# MTX_Tap_an_er_V11.net
KiCad netlist of a schematic drawn in EAGLE
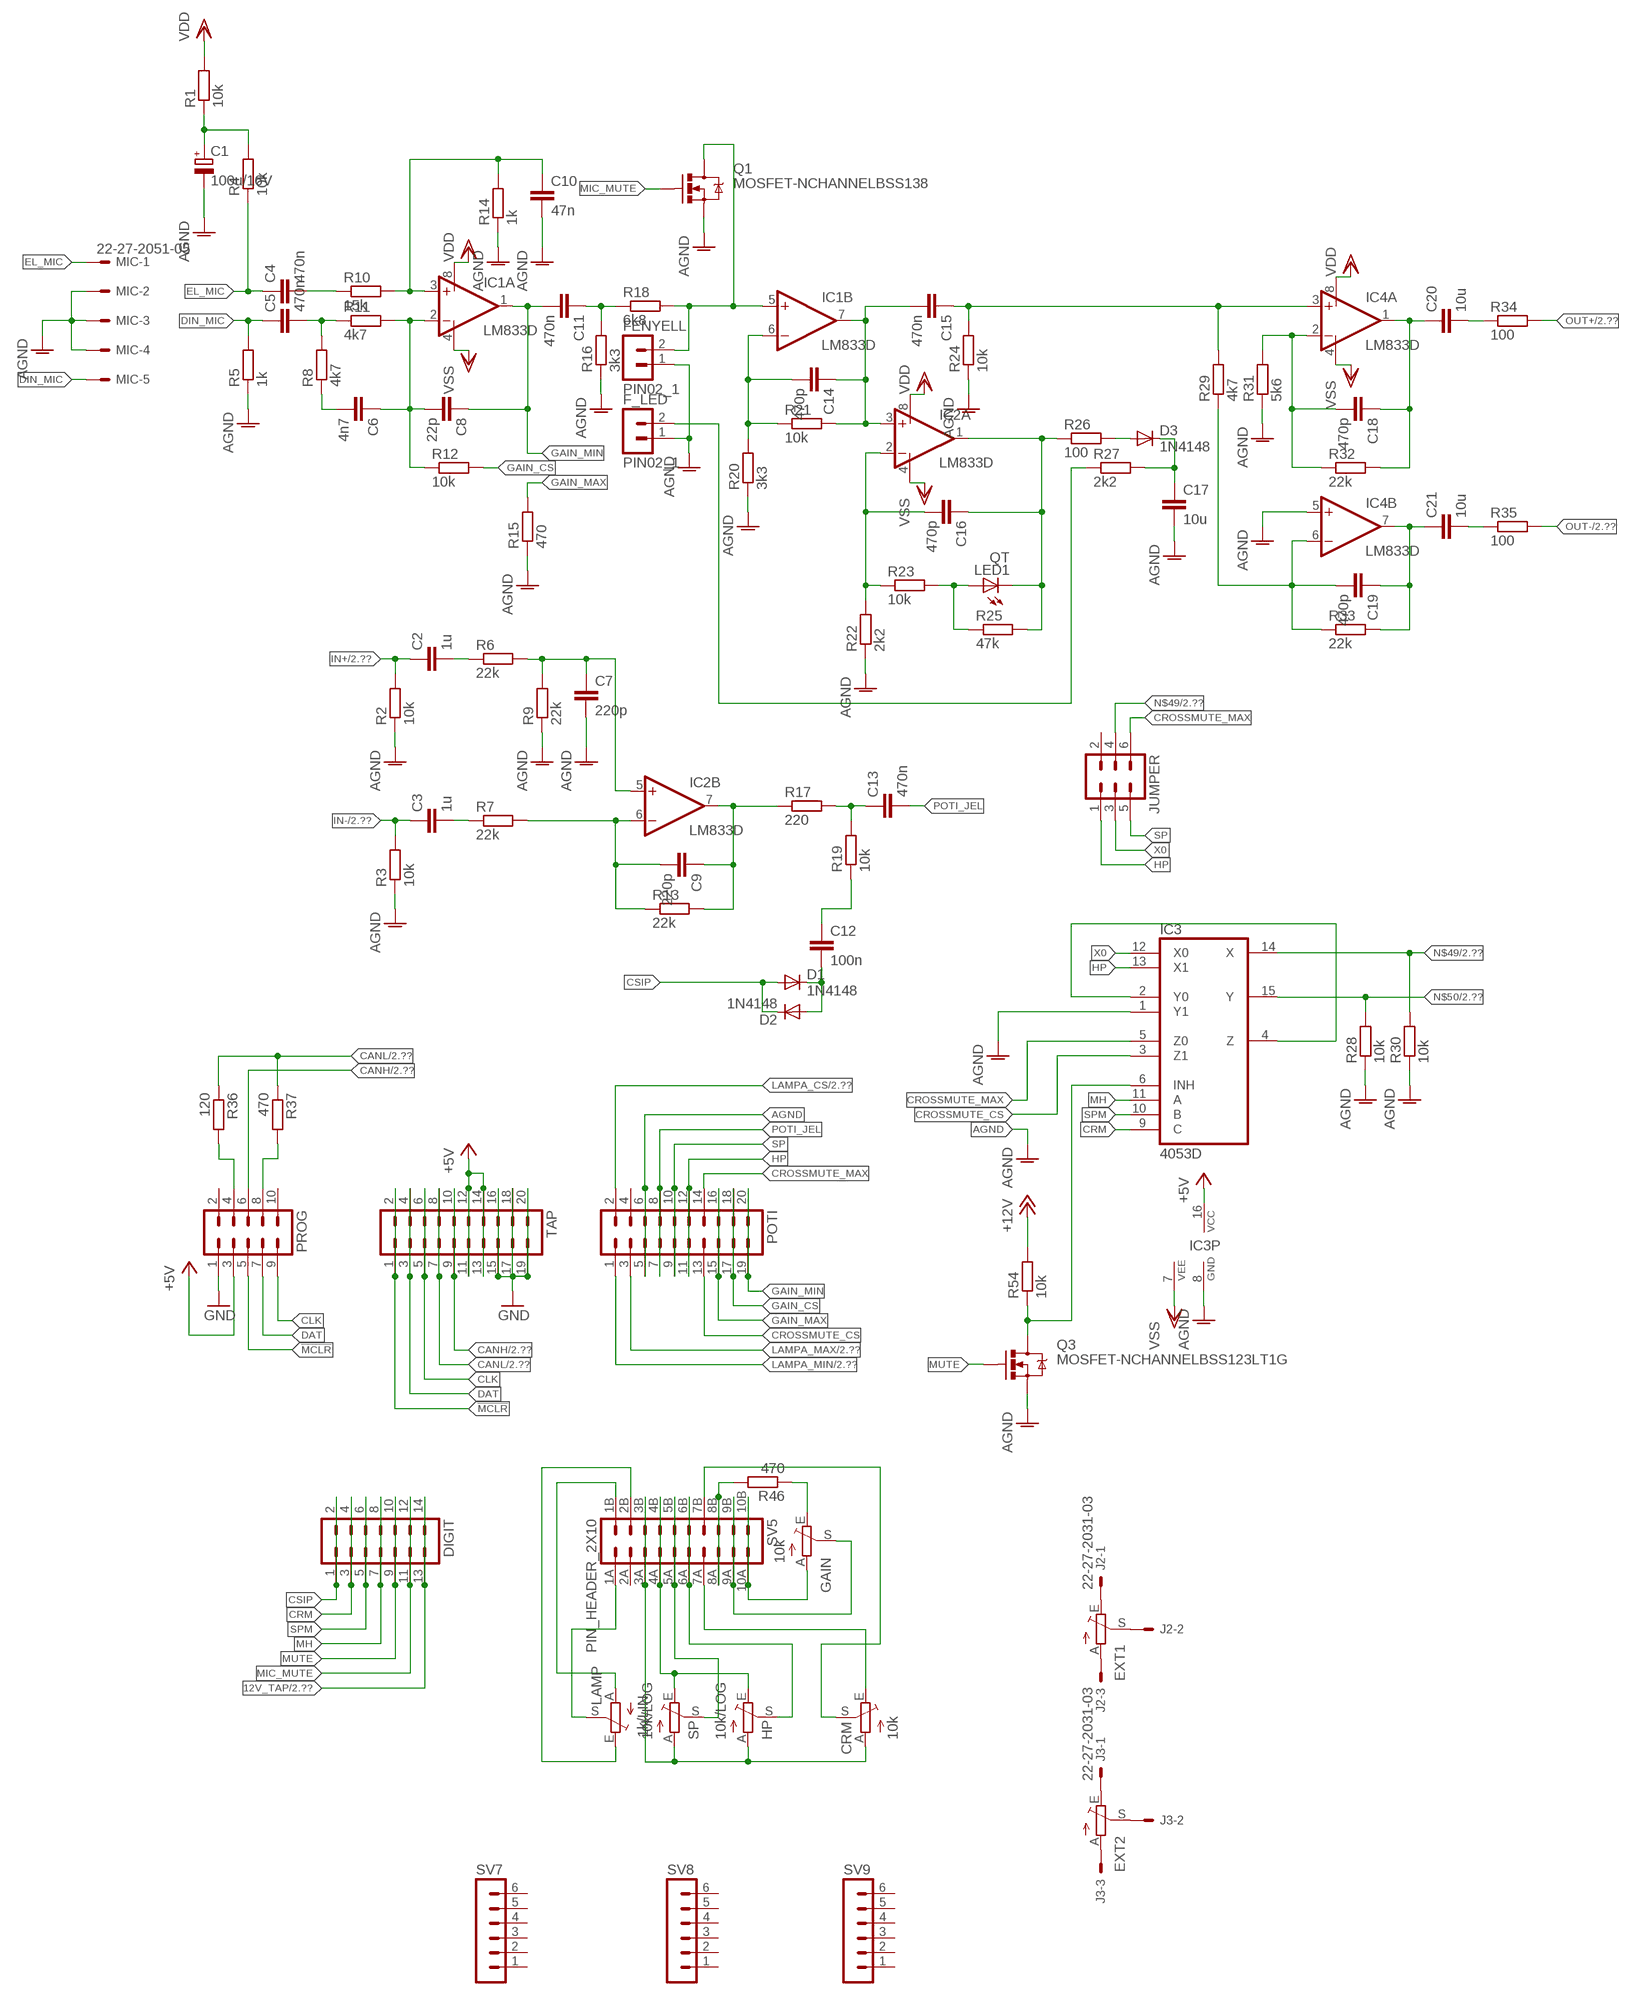
[diagram p0: schematic, sheet 1]
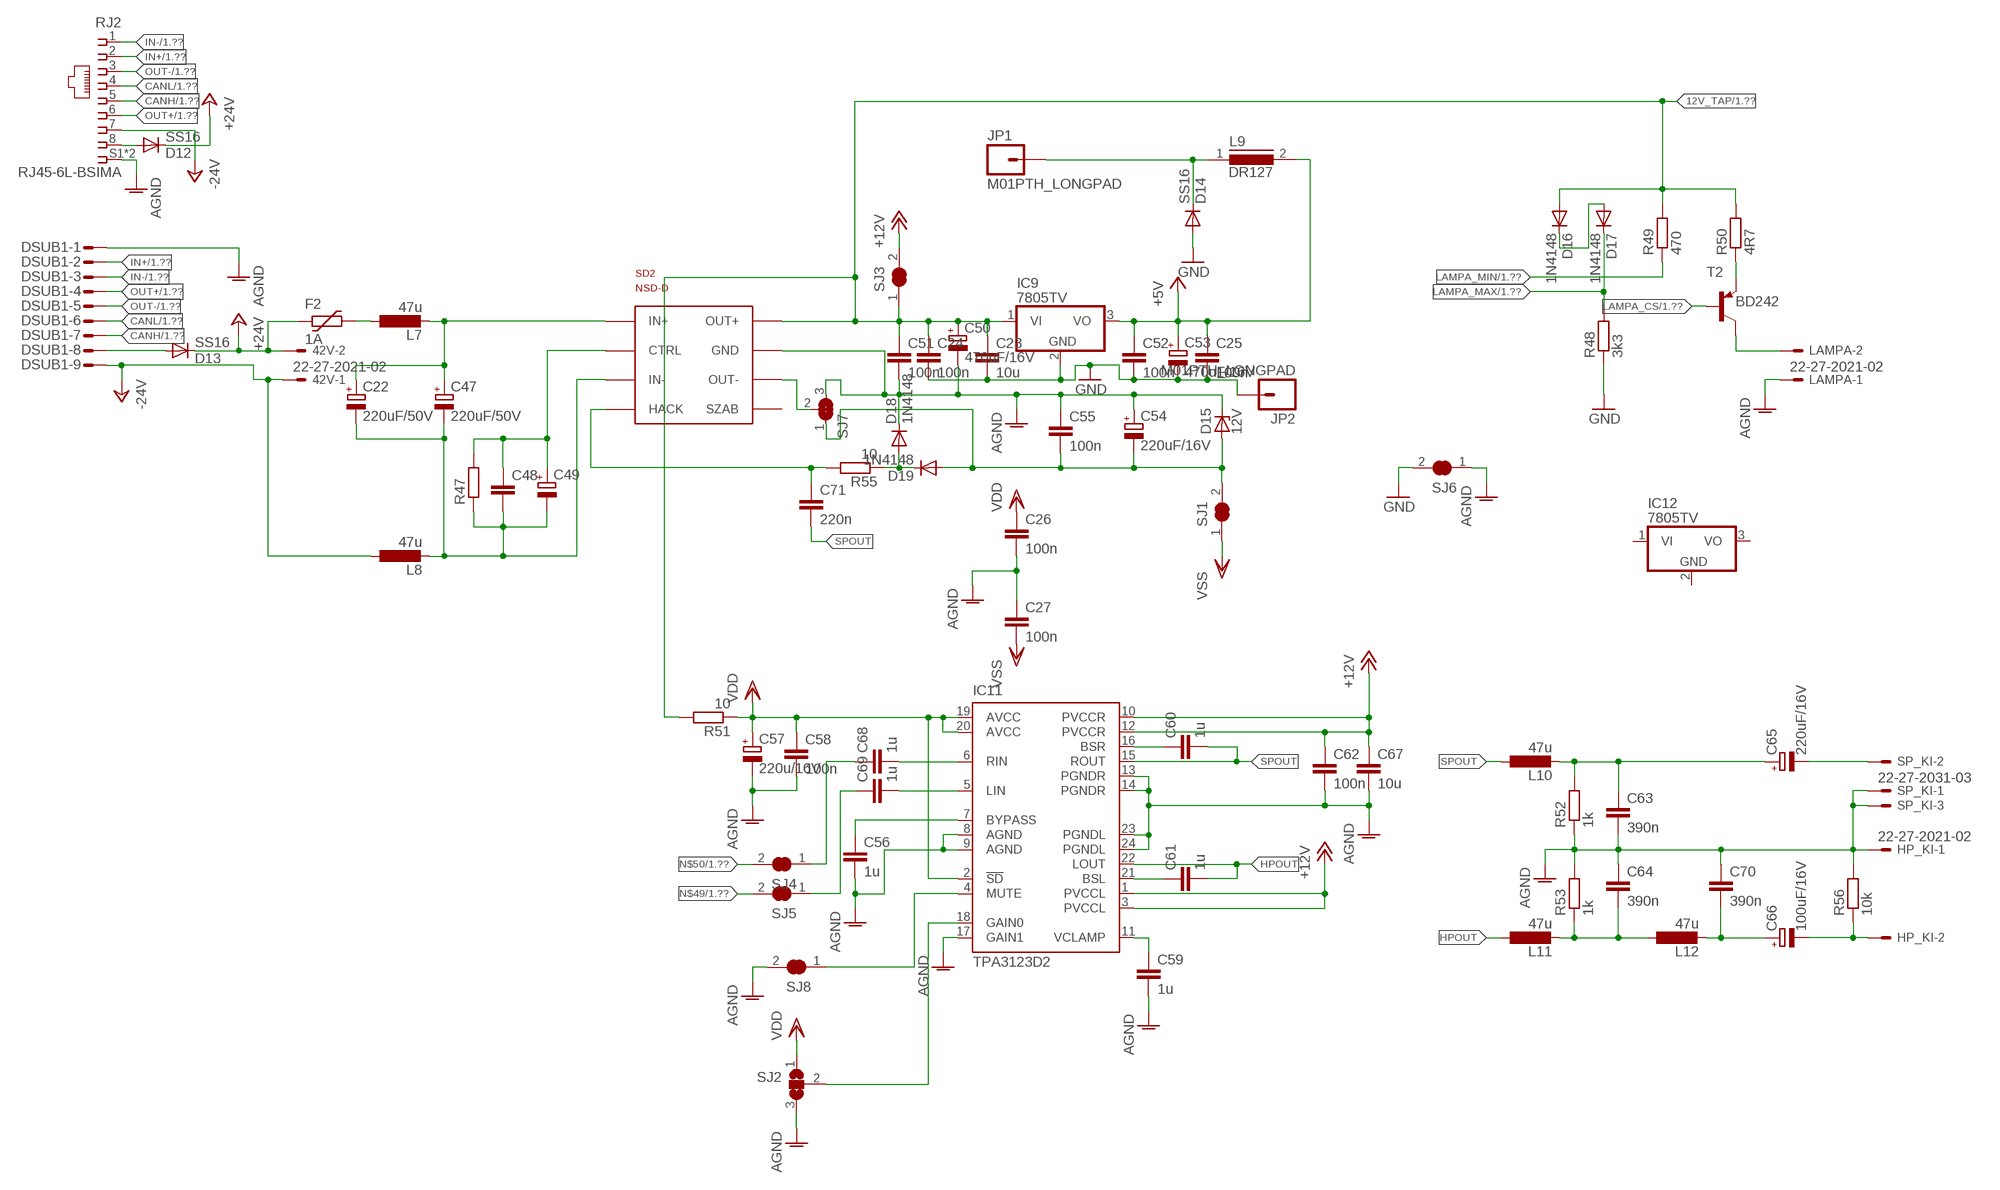
[diagram p1: schematic, sheet 2]

(export (version "E")
  (design (tool "Eeschema 10.0.6"))
  (components
    (comp (ref "42V")
      (value "22-27-2021-02")
      (footprint "eagle-import:6410-02")
      (libsource (lib "eagle-import") (part "22-?-0227-2021"))
    )
    (comp (ref "C22")
      (value "220uF/50V")
      (footprint "eagle-import:E3,5-8")
      (libsource (lib "eagle-import") (part "CPOL-EUE3.5-8"))
    )
    (comp (ref "C23")
      (value "10u")
      (footprint "eagle-import:C0805")
      (libsource (lib "eagle-import") (part "C-EUC0805"))
    )
    (comp (ref "C24")
      (value "100n")
      (footprint "eagle-import:C0805")
      (libsource (lib "eagle-import") (part "C-EUC0805"))
    )
    (comp (ref "C25")
      (value "100n")
      (footprint "eagle-import:C0805")
      (libsource (lib "eagle-import") (part "C-EUC0805"))
    )
    (comp (ref "C26")
      (value "100n")
      (footprint "eagle-import:C0805")
      (libsource (lib "eagle-import") (part "C-EUC0805"))
    )
    (comp (ref "C27")
      (value "100n")
      (footprint "eagle-import:C0805")
      (libsource (lib "eagle-import") (part "C-EUC0805"))
    )
    (comp (ref "C47")
      (value "220uF/50V")
      (footprint "eagle-import:E3,5-8")
      (libsource (lib "eagle-import") (part "CPOL-EUE3.5-8"))
    )
    (comp (ref "C48")
      (value "C-EUC0805")
      (footprint "eagle-import:C0805")
      (libsource (lib "eagle-import") (part "C-EUC0805"))
    )
    (comp (ref "C49")
      (value "CPOL-EUE2.5-5")
      (footprint "eagle-import:E2,5-5")
      (libsource (lib "eagle-import") (part "CPOL-EUE2.5-5"))
    )
    (comp (ref "C50")
      (value "470uF/16V")
      (footprint "eagle-import:E3,5-8")
      (libsource (lib "eagle-import") (part "CPOL-EUE3.5-8"))
    )
    (comp (ref "C51")
      (value "100n")
      (footprint "eagle-import:C0805")
      (libsource (lib "eagle-import") (part "C-EUC0805"))
    )
    (comp (ref "C52")
      (value "100n")
      (footprint "eagle-import:C0805")
      (libsource (lib "eagle-import") (part "C-EUC0805"))
    )
    (comp (ref "C53")
      (value "470uF/16V")
      (footprint "eagle-import:E3,5-8")
      (libsource (lib "eagle-import") (part "CPOL-EUE3.5-8"))
    )
    (comp (ref "C54")
      (value "220uF/16V")
      (footprint "eagle-import:E2,5-7")
      (libsource (lib "eagle-import") (part "CPOL-EUE2.5-7"))
    )
    (comp (ref "C55")
      (value "100n")
      (footprint "eagle-import:C0805")
      (libsource (lib "eagle-import") (part "C-EUC0805"))
    )
    (comp (ref "C56")
      (value "1u")
      (footprint "eagle-import:C0805")
      (libsource (lib "eagle-import") (part "C-EUC0805"))
    )
    (comp (ref "C57")
      (value "220u/16V")
      (footprint "eagle-import:E2,5-7")
      (libsource (lib "eagle-import") (part "CPOL-EUE2.5-7"))
    )
    (comp (ref "C58")
      (value "100n")
      (footprint "eagle-import:C0805")
      (libsource (lib "eagle-import") (part "C-EUC0805"))
    )
    (comp (ref "C59")
      (value "1u")
      (footprint "eagle-import:C0805")
      (libsource (lib "eagle-import") (part "C-EUC0805"))
    )
    (comp (ref "C60")
      (value "1u")
      (footprint "eagle-import:C0805")
      (libsource (lib "eagle-import") (part "C-EUC0805"))
    )
    (comp (ref "C61")
      (value "1u")
      (footprint "eagle-import:C0805")
      (libsource (lib "eagle-import") (part "C-EUC0805"))
    )
    (comp (ref "C62")
      (value "100n")
      (footprint "eagle-import:C0805")
      (libsource (lib "eagle-import") (part "C-EUC0805"))
    )
    (comp (ref "C63")
      (value "390n")
      (footprint "eagle-import:C0805")
      (libsource (lib "eagle-import") (part "C-EUC0805"))
    )
    (comp (ref "C64")
      (value "390n")
      (footprint "eagle-import:C0805")
      (libsource (lib "eagle-import") (part "C-EUC0805"))
    )
    (comp (ref "C65")
      (value "220uF/16V")
      (footprint "eagle-import:E2,5-7")
      (libsource (lib "eagle-import") (part "CPOL-EUE2.5-7"))
    )
    (comp (ref "C66")
      (value "100uF/16V")
      (footprint "eagle-import:E2,5-6")
      (libsource (lib "eagle-import") (part "CPOL-EUE2.5-6"))
    )
    (comp (ref "C67")
      (value "10u")
      (footprint "eagle-import:C0805")
      (libsource (lib "eagle-import") (part "C-EUC0805"))
    )
    (comp (ref "C68")
      (value "1u")
      (footprint "eagle-import:C0805")
      (libsource (lib "eagle-import") (part "C-EUC0805"))
    )
    (comp (ref "C69")
      (value "1u")
      (footprint "eagle-import:C0805")
      (libsource (lib "eagle-import") (part "C-EUC0805"))
    )
    (comp (ref "C70")
      (value "390n")
      (footprint "eagle-import:C0805")
      (libsource (lib "eagle-import") (part "C-EUC0805"))
    )
    (comp (ref "C71")
      (value "220n")
      (footprint "eagle-import:C0805")
      (libsource (lib "eagle-import") (part "C-EUC0805"))
    )
    (comp (ref "D12")
      (value "SS16")
      (footprint "eagle-import:DO-214AC")
      (libsource (lib "eagle-import") (part "dp_devices_DIODE-DO-214AC"))
    )
    (comp (ref "D13")
      (value "SS16")
      (footprint "eagle-import:DO-214AC")
      (libsource (lib "eagle-import") (part "dp_devices_DIODE-DO-214AC"))
    )
    (comp (ref "D14")
      (value "SS16")
      (footprint "eagle-import:DO-214AC")
      (libsource (lib "eagle-import") (part "dp_devices_DIODE-DO-214AC"))
    )
    (comp (ref "D15")
      (value "12V")
      (footprint "eagle-import:SOD80C")
      (libsource (lib "eagle-import") (part "ZENER-DIODESOD80C"))
    )
    (comp (ref "D16")
      (value "1N4148")
      (footprint "eagle-import:SOD80C")
      (libsource (lib "eagle-import") (part "DIODE-SOD80C"))
    )
    (comp (ref "D17")
      (value "1N4148")
      (footprint "eagle-import:SOD80C")
      (libsource (lib "eagle-import") (part "DIODE-SOD80C"))
    )
    (comp (ref "D18")
      (value "1N4148")
      (footprint "eagle-import:SOD80C")
      (libsource (lib "eagle-import") (part "DIODE-SOD80C"))
    )
    (comp (ref "D19")
      (value "1N4148")
      (footprint "eagle-import:SOD80C")
      (libsource (lib "eagle-import") (part "DIODE-SOD80C"))
    )
    (comp (ref "DSUB1")
      (value "M09-182S")
      (footprint "eagle-import:182-009-MALE")
      (libsource (lib "eagle-import") (part "M09?S-182"))
    )
    (comp (ref "F2")
      (value "1A")
      (footprint "eagle-import:PTC1812L")
      (libsource (lib "eagle-import") (part "FUSE_PTC-1812"))
    )
    (comp (ref "HP_KI")
      (value "22-27-2021-02")
      (footprint "eagle-import:6410-02")
      (libsource (lib "eagle-import") (part "22-?-0227-2021"))
    )
    (comp (ref "IC9")
      (value "7805TV")
      (footprint "eagle-import:TO220V")
      (libsource (lib "eagle-import") (part "78TV05"))
    )
    (comp (ref "IC11")
      (value "TPA3123D2")
      (footprint "eagle-import:PWP-TSSOP24")
      (fields (field (name "MPN") "TPA3123D2PWP"))
      (libsource (lib "eagle-import") (part "TPA3123D2"))
    )
    (comp (ref "IC12")
      (value "7805TV")
      (footprint "eagle-import:TO220V")
      (libsource (lib "eagle-import") (part "78TV05"))
    )
    (comp (ref "JP1")
      (value "M01PTH_LONGPAD")
      (footprint "eagle-import:1X01_LONGPAD")
      (libsource (lib "eagle-import") (part "M01PTH_LONGPAD"))
    )
    (comp (ref "JP2")
      (value "M01PTH_LONGPAD")
      (footprint "eagle-import:1X01_LONGPAD")
      (libsource (lib "eagle-import") (part "M01PTH_LONGPAD"))
    )
    (comp (ref "L7")
      (value "47u")
      (footprint "eagle-import:PIS2816")
      (libsource (lib "eagle-import") (part "L-EUPIS2816"))
    )
    (comp (ref "L8")
      (value "47u")
      (footprint "eagle-import:PIS2816")
      (libsource (lib "eagle-import") (part "L-EUPIS2816"))
    )
    (comp (ref "L9")
      (value "DR127")
      (footprint "eagle-import:DR127")
      (libsource (lib "eagle-import") (part "DR127"))
    )
    (comp (ref "L10")
      (value "47u")
      (footprint "eagle-import:PIS2816")
      (libsource (lib "eagle-import") (part "L-EUPIS2816"))
    )
    (comp (ref "L11")
      (value "47u")
      (footprint "eagle-import:PIS2816")
      (libsource (lib "eagle-import") (part "L-EUPIS2816"))
    )
    (comp (ref "L12")
      (value "47u")
      (footprint "eagle-import:PIS2816")
      (libsource (lib "eagle-import") (part "L-EUPIS2816"))
    )
    (comp (ref "LAMPA")
      (value "22-27-2021-02")
      (footprint "eagle-import:6410-02")
      (libsource (lib "eagle-import") (part "22-?-0227-2021"))
    )
    (comp (ref "R47")
      (value "R-EU_R0805")
      (footprint "eagle-import:R0805")
      (libsource (lib "eagle-import") (part "R-EU_R0805"))
    )
    (comp (ref "R48")
      (value "3k3")
      (footprint "eagle-import:R0805")
      (libsource (lib "eagle-import") (part "R-EU_R0805"))
    )
    (comp (ref "R49")
      (value "470")
      (footprint "eagle-import:R0805")
      (libsource (lib "eagle-import") (part "R-EU_R0805"))
    )
    (comp (ref "R50")
      (value "4R7")
      (footprint "eagle-import:R0805")
      (libsource (lib "eagle-import") (part "R-EU_R0805"))
    )
    (comp (ref "R51")
      (value "10")
      (footprint "eagle-import:R1210")
      (libsource (lib "eagle-import") (part "R-EU_R1210"))
    )
    (comp (ref "R52")
      (value "1k")
      (footprint "eagle-import:R0805")
      (libsource (lib "eagle-import") (part "R-EU_R0805"))
    )
    (comp (ref "R53")
      (value "1k")
      (footprint "eagle-import:R0805")
      (libsource (lib "eagle-import") (part "R-EU_R0805"))
    )
    (comp (ref "R55")
      (value "10")
      (footprint "eagle-import:R0805")
      (libsource (lib "eagle-import") (part "R-EU_R0805"))
    )
    (comp (ref "R56")
      (value "10k")
      (footprint "eagle-import:R0805")
      (libsource (lib "eagle-import") (part "R-EU_R0805"))
    )
    (comp (ref "RJ2")
      (value "RJ45-6L-BSIMA")
      (footprint "eagle-import:RJ45")
      (fields (field (name "MPN") "RJ45-6L-B"))
      (libsource (lib "eagle-import") (part "RJ45SIMA-6L-B"))
    )
    (comp (ref "SD2")
      (value "NSD-D")
      (footprint "eagle-import:NSD-D")
      (libsource (lib "eagle-import") (part "NSD-D"))
    )
    (comp (ref "SJ1")
      (value "SOLDERJUMPER_CLOSED")
      (footprint "eagle-import:SOLDERJUMPER_CLOSEDWIRE")
      (libsource (lib "eagle-import") (part "SOLDERJUMPER_CLOSED"))
    )
    (comp (ref "SJ2")
      (value "SJ2W")
      (footprint "eagle-import:SJ_2")
      (libsource (lib "eagle-import") (part "SJ2W"))
    )
    (comp (ref "SJ3")
      (value "SOLDERJUMPER_CLOSED")
      (footprint "eagle-import:SOLDERJUMPER_CLOSEDWIRE")
      (libsource (lib "eagle-import") (part "SOLDERJUMPER_CLOSED"))
    )
    (comp (ref "SJ4")
      (value "SOLDERJUMPER_CLOSED")
      (footprint "eagle-import:SOLDERJUMPER_CLOSEDWIRE")
      (libsource (lib "eagle-import") (part "SOLDERJUMPER_CLOSED"))
    )
    (comp (ref "SJ5")
      (value "SOLDERJUMPER_CLOSED")
      (footprint "eagle-import:SOLDERJUMPER_CLOSEDWIRE")
      (libsource (lib "eagle-import") (part "SOLDERJUMPER_CLOSED"))
    )
    (comp (ref "SJ6")
      (value "SOLDERJUMPER_CLOSED")
      (footprint "eagle-import:SOLDERJUMPER_CLOSEDWIRE")
      (libsource (lib "eagle-import") (part "SOLDERJUMPER_CLOSED"))
    )
    (comp (ref "SJ7")
      (value "SOLDERJUMPER_2WAY")
      (footprint "eagle-import:SOLDERJUMPER_2WAY_OPEN_NOPASTE")
      (libsource (lib "eagle-import") (part "SOLDERJUMPER_2WAY"))
    )
    (comp (ref "SJ8")
      (value "SOLDERJUMPER_CLOSED")
      (footprint "eagle-import:SOLDERJUMPER_CLOSEDWIRE")
      (libsource (lib "eagle-import") (part "SOLDERJUMPER_CLOSED"))
    )
    (comp (ref "SP_KI")
      (value "22-27-2031-03")
      (footprint "eagle-import:6410-03")
      (libsource (lib "eagle-import") (part "22-?-0327-2031"))
    )
    (comp (ref "T2")
      (value "BD242")
      (footprint "eagle-import:TO220V")
      (libsource (lib "eagle-import") (part "-PNP-TO220V"))
    )
    (comp (ref "C1")
      (value "100u/16V")
      (footprint "eagle-import:E2,5-5")
      (libsource (lib "eagle-import") (part "CPOL-EUE2.5-5"))
    )
    (comp (ref "C2")
      (value "1u")
      (footprint "eagle-import:C0805")
      (libsource (lib "eagle-import") (part "C-EUC0805"))
    )
    (comp (ref "C3")
      (value "1u")
      (footprint "eagle-import:C0805")
      (libsource (lib "eagle-import") (part "C-EUC0805"))
    )
    (comp (ref "C4")
      (value "470n")
      (footprint "eagle-import:C0805")
      (libsource (lib "eagle-import") (part "C-EUC0805"))
    )
    (comp (ref "C5")
      (value "470n")
      (footprint "eagle-import:C0805")
      (libsource (lib "eagle-import") (part "C-EUC0805"))
    )
    (comp (ref "C6")
      (value "4n7")
      (footprint "eagle-import:C0805")
      (libsource (lib "eagle-import") (part "C-EUC0805"))
    )
    (comp (ref "C7")
      (value "220p")
      (footprint "eagle-import:C0805")
      (libsource (lib "eagle-import") (part "C-EUC0805"))
    )
    (comp (ref "C8")
      (value "22p")
      (footprint "eagle-import:C0805")
      (libsource (lib "eagle-import") (part "C-EUC0805"))
    )
    (comp (ref "C9")
      (value "220p")
      (footprint "eagle-import:C0805")
      (libsource (lib "eagle-import") (part "C-EUC0805"))
    )
    (comp (ref "C10")
      (value "47n")
      (footprint "eagle-import:C0805")
      (libsource (lib "eagle-import") (part "C-EUC0805"))
    )
    (comp (ref "C11")
      (value "470n")
      (footprint "eagle-import:C0805")
      (libsource (lib "eagle-import") (part "C-EUC0805"))
    )
    (comp (ref "C12")
      (value "100n")
      (footprint "eagle-import:C0805")
      (libsource (lib "eagle-import") (part "C-EUC0805"))
    )
    (comp (ref "C13")
      (value "470n")
      (footprint "eagle-import:C0805")
      (libsource (lib "eagle-import") (part "C-EUC0805"))
    )
    (comp (ref "C14")
      (value "470p")
      (footprint "eagle-import:C0805")
      (libsource (lib "eagle-import") (part "C-EUC0805"))
    )
    (comp (ref "C15")
      (value "470n")
      (footprint "eagle-import:C0805")
      (libsource (lib "eagle-import") (part "C-EUC0805"))
    )
    (comp (ref "C16")
      (value "470p")
      (footprint "eagle-import:C0805")
      (libsource (lib "eagle-import") (part "C-EUC0805"))
    )
    (comp (ref "C17")
      (value "10u")
      (footprint "eagle-import:C0805")
      (libsource (lib "eagle-import") (part "C-EUC0805"))
    )
    (comp (ref "C18")
      (value "470p")
      (footprint "eagle-import:C0805")
      (libsource (lib "eagle-import") (part "C-EUC0805"))
    )
    (comp (ref "C19")
      (value "470p")
      (footprint "eagle-import:C0805")
      (libsource (lib "eagle-import") (part "C-EUC0805"))
    )
    (comp (ref "C20")
      (value "10u")
      (footprint "eagle-import:C0805")
      (libsource (lib "eagle-import") (part "C-EUC0805"))
    )
    (comp (ref "C21")
      (value "10u")
      (footprint "eagle-import:C0805")
      (libsource (lib "eagle-import") (part "C-EUC0805"))
    )
    (comp (ref "CRM")
      (value "10k")
      (footprint "eagle-import:PT-10")
      (libsource (lib "eagle-import") (part "TRIM_EU-PT10"))
    )
    (comp (ref "D1")
      (value "1N4148")
      (footprint "eagle-import:SOD80C")
      (libsource (lib "eagle-import") (part "DIODE-SOD80C"))
    )
    (comp (ref "D2")
      (value "1N4148")
      (footprint "eagle-import:SOD80C")
      (libsource (lib "eagle-import") (part "DIODE-SOD80C"))
    )
    (comp (ref "D3")
      (value "1N4148")
      (footprint "eagle-import:SOD80C")
      (libsource (lib "eagle-import") (part "DIODE-SOD80C"))
    )
    (comp (ref "DIGIT")
      (value "MA07-2")
      (footprint "eagle-import:MA07-2")
      (libsource (lib "eagle-import") (part "MA07-2"))
    )
    (comp (ref "EXT1")
      (value "TRIM_EU-PT10")
      (footprint "eagle-import:PT-10")
      (libsource (lib "eagle-import") (part "TRIM_EU-PT10"))
    )
    (comp (ref "EXT2")
      (value "TRIM_EU-PT10")
      (footprint "eagle-import:PT-10")
      (libsource (lib "eagle-import") (part "TRIM_EU-PT10"))
    )
    (comp (ref "FENYELL")
      (value "PIN02_1")
      (footprint "eagle-import:PIN02_1")
      (libsource (lib "eagle-import") (part "PIN02_1"))
    )
    (comp (ref "F_LED")
      (value "PIN02_1")
      (footprint "eagle-import:PIN02_1")
      (libsource (lib "eagle-import") (part "PIN02_1"))
    )
    (comp (ref "GAIN")
      (value "10k")
      (footprint "eagle-import:PT-10")
      (libsource (lib "eagle-import") (part "TRIM_EU-PT10"))
    )
    (comp (ref "HP")
      (value "10k/LOG")
      (footprint "eagle-import:POT_NAR")
      (libsource (lib "eagle-import") (part "TRIM_EU-POT_WHOLE"))
    )
    (comp (ref "IC1")
      (value "LM833D")
      (footprint "eagle-import:SO08")
      (libsource (lib "eagle-import") (part "LM833D"))
    )
    (comp (ref "IC2")
      (value "LM833D")
      (footprint "eagle-import:SO08")
      (libsource (lib "eagle-import") (part "LM833D"))
    )
    (comp (ref "IC3")
      (value "4053D")
      (footprint "eagle-import:SO16")
      (libsource (lib "eagle-import") (part "4053D"))
    )
    (comp (ref "IC4")
      (value "LM833D")
      (footprint "eagle-import:SO08")
      (libsource (lib "eagle-import") (part "LM833D"))
    )
    (comp (ref "J2")
      (value "22-27-2031-03")
      (footprint "eagle-import:6410-03")
      (libsource (lib "eagle-import") (part "22-?-0327-2031"))
    )
    (comp (ref "J3")
      (value "22-27-2031-03")
      (footprint "eagle-import:6410-03")
      (libsource (lib "eagle-import") (part "22-?-0327-2031"))
    )
    (comp (ref "JUMPER")
      (value "MA03-2")
      (footprint "eagle-import:MA03-2")
      (libsource (lib "eagle-import") (part "MA03-2"))
    )
    (comp (ref "LAMP")
      (value "1k/LIN")
      (footprint "eagle-import:POT_NAR")
      (libsource (lib "eagle-import") (part "TRIM_EU-POT_WHOLE"))
    )
    (comp (ref "LED1")
      (value "QT")
      (footprint "eagle-import:LED3MM")
      (libsource (lib "eagle-import") (part "LED3MM"))
    )
    (comp (ref "MIC")
      (value "22-27-2051-05")
      (footprint "eagle-import:6410-05")
      (libsource (lib "eagle-import") (part "22-?-0527-2051"))
    )
    (comp (ref "POTI")
      (value "MA10-2")
      (footprint "eagle-import:MA10-2")
      (libsource (lib "eagle-import") (part "MA10-2"))
    )
    (comp (ref "PROG")
      (value "ML10L")
      (footprint "eagle-import:ML10L")
      (libsource (lib "eagle-import") (part "ML10L"))
    )
    (comp (ref "Q1")
      (value "MOSFET-NCHANNELBSS138")
      (footprint "eagle-import:SOT23")
      (libsource (lib "eagle-import") (part "MOSFET-NCHANNELBSS138"))
    )
    (comp (ref "Q3")
      (value "MOSFET-NCHANNELBSS123LT1G")
      (footprint "eagle-import:SOT23")
      (libsource (lib "eagle-import") (part "MOSFET-NCHANNELBSS123LT1G"))
    )
    (comp (ref "R1")
      (value "10k")
      (footprint "eagle-import:R0805")
      (libsource (lib "eagle-import") (part "R-EU_R0805"))
    )
    (comp (ref "R2")
      (value "10k")
      (footprint "eagle-import:R0805")
      (libsource (lib "eagle-import") (part "R-EU_R0805"))
    )
    (comp (ref "R3")
      (value "10k")
      (footprint "eagle-import:R0805")
      (libsource (lib "eagle-import") (part "R-EU_R0805"))
    )
    (comp (ref "R4")
      (value "10k")
      (footprint "eagle-import:R0805")
      (libsource (lib "eagle-import") (part "R-EU_R0805"))
    )
    (comp (ref "R5")
      (value "1k")
      (footprint "eagle-import:R0805")
      (libsource (lib "eagle-import") (part "R-EU_R0805"))
    )
    (comp (ref "R6")
      (value "22k")
      (footprint "eagle-import:R0805")
      (libsource (lib "eagle-import") (part "R-EU_R0805"))
    )
    (comp (ref "R7")
      (value "22k")
      (footprint "eagle-import:R0805")
      (libsource (lib "eagle-import") (part "R-EU_R0805"))
    )
    (comp (ref "R8")
      (value "4k7")
      (footprint "eagle-import:R0805")
      (libsource (lib "eagle-import") (part "R-EU_R0805"))
    )
    (comp (ref "R9")
      (value "22k")
      (footprint "eagle-import:R0805")
      (libsource (lib "eagle-import") (part "R-EU_R0805"))
    )
    (comp (ref "R10")
      (value "15k")
      (footprint "eagle-import:R0805")
      (libsource (lib "eagle-import") (part "R-EU_R0805"))
    )
    (comp (ref "R11")
      (value "4k7")
      (footprint "eagle-import:R0805")
      (libsource (lib "eagle-import") (part "R-EU_R0805"))
    )
    (comp (ref "R12")
      (value "10k")
      (footprint "eagle-import:R0805")
      (libsource (lib "eagle-import") (part "R-EU_R0805"))
    )
    (comp (ref "R13")
      (value "22k")
      (footprint "eagle-import:R0805")
      (libsource (lib "eagle-import") (part "R-EU_R0805"))
    )
    (comp (ref "R14")
      (value "1k")
      (footprint "eagle-import:R0805")
      (libsource (lib "eagle-import") (part "R-EU_R0805"))
    )
    (comp (ref "R15")
      (value "470")
      (footprint "eagle-import:R0805")
      (libsource (lib "eagle-import") (part "R-EU_R0805"))
    )
    (comp (ref "R16")
      (value "3k3")
      (footprint "eagle-import:R0805")
      (libsource (lib "eagle-import") (part "R-EU_R0805"))
    )
    (comp (ref "R17")
      (value "220")
      (footprint "eagle-import:R0805")
      (libsource (lib "eagle-import") (part "R-EU_R0805"))
    )
    (comp (ref "R18")
      (value "6k8")
      (footprint "eagle-import:R0805")
      (libsource (lib "eagle-import") (part "R-EU_R0805"))
    )
    (comp (ref "R19")
      (value "10k")
      (footprint "eagle-import:R0805")
      (libsource (lib "eagle-import") (part "R-EU_R0805"))
    )
    (comp (ref "R20")
      (value "3k3")
      (footprint "eagle-import:R0805")
      (libsource (lib "eagle-import") (part "R-EU_R0805"))
    )
    (comp (ref "R21")
      (value "10k")
      (footprint "eagle-import:R0805")
      (libsource (lib "eagle-import") (part "R-EU_R0805"))
    )
    (comp (ref "R22")
      (value "2k2")
      (footprint "eagle-import:R0805")
      (libsource (lib "eagle-import") (part "R-EU_R0805"))
    )
    (comp (ref "R23")
      (value "10k")
      (footprint "eagle-import:R0805")
      (libsource (lib "eagle-import") (part "R-EU_R0805"))
    )
    (comp (ref "R24")
      (value "10k")
      (footprint "eagle-import:R0805")
      (libsource (lib "eagle-import") (part "R-EU_R0805"))
    )
    (comp (ref "R25")
      (value "47k")
      (footprint "eagle-import:R0805")
      (libsource (lib "eagle-import") (part "R-EU_R0805"))
    )
    (comp (ref "R26")
      (value "100")
      (footprint "eagle-import:R0805")
      (libsource (lib "eagle-import") (part "R-EU_R0805"))
    )
    (comp (ref "R27")
      (value "2k2")
      (footprint "eagle-import:R0805")
      (libsource (lib "eagle-import") (part "R-EU_R0805"))
    )
    (comp (ref "R28")
      (value "10k")
      (footprint "eagle-import:R0805")
      (libsource (lib "eagle-import") (part "R-EU_R0805"))
    )
    (comp (ref "R29")
      (value "4k7")
      (footprint "eagle-import:R0805")
      (libsource (lib "eagle-import") (part "R-EU_R0805"))
    )
    (comp (ref "R30")
      (value "10k")
      (footprint "eagle-import:R0805")
      (libsource (lib "eagle-import") (part "R-EU_R0805"))
    )
    (comp (ref "R31")
      (value "5k6")
      (footprint "eagle-import:R0805")
      (libsource (lib "eagle-import") (part "R-EU_R0805"))
    )
    (comp (ref "R32")
      (value "22k")
      (footprint "eagle-import:R0805")
      (libsource (lib "eagle-import") (part "R-EU_R0805"))
    )
    (comp (ref "R33")
      (value "22k")
      (footprint "eagle-import:R0805")
      (libsource (lib "eagle-import") (part "R-EU_R0805"))
    )
    (comp (ref "R34")
      (value "100")
      (footprint "eagle-import:R0805")
      (libsource (lib "eagle-import") (part "R-EU_R0805"))
    )
    (comp (ref "R35")
      (value "100")
      (footprint "eagle-import:R0805")
      (libsource (lib "eagle-import") (part "R-EU_R0805"))
    )
    (comp (ref "R36")
      (value "120")
      (footprint "eagle-import:R0805")
      (libsource (lib "eagle-import") (part "R-EU_R0805"))
    )
    (comp (ref "R37")
      (value "470")
      (footprint "eagle-import:R0805")
      (libsource (lib "eagle-import") (part "R-EU_R0805"))
    )
    (comp (ref "R46")
      (value "470")
      (footprint "eagle-import:R0805")
      (libsource (lib "eagle-import") (part "R-EU_R0805"))
    )
    (comp (ref "R54")
      (value "10k")
      (footprint "eagle-import:R0805")
      (libsource (lib "eagle-import") (part "R-EU_R0805"))
    )
    (comp (ref "SP")
      (value "10k/LOG")
      (footprint "eagle-import:POT_NAR")
      (libsource (lib "eagle-import") (part "TRIM_EU-POT_WHOLE"))
    )
    (comp (ref "SV5")
      (value "PIN_HEADER_2X10")
      (footprint "eagle-import:PIN_HEADER_2X10SMD")
      (libsource (lib "eagle-import") (part "PIN_HEADER_2X10"))
    )
    (comp (ref "SV7")
      (value "MA06-1")
      (footprint "eagle-import:MA06-1")
      (libsource (lib "eagle-import") (part "MA06-1"))
    )
    (comp (ref "SV8")
      (value "MA06-1")
      (footprint "eagle-import:MA06-1")
      (libsource (lib "eagle-import") (part "MA06-1"))
    )
    (comp (ref "SV9")
      (value "MA06-1")
      (footprint "eagle-import:MA06-1")
      (libsource (lib "eagle-import") (part "MA06-1"))
    )
    (comp (ref "TAP")
      (value "MA10-2")
      (footprint "eagle-import:MA10-2")
      (libsource (lib "eagle-import") (part "MA10-2"))
    )
  )
  (nets
    (net (code "1") (name "+5V") (class "Default")
      (node (ref "C25") (pin "1") (pinfunction "1_1") (pintype "passive"))
      (node (ref "C52") (pin "1") (pinfunction "1_1") (pintype "passive"))
      (node (ref "C53") (pin "+") (pinfunction "+_+") (pintype "passive"))
      (node (ref "IC3") (pin "16") (pinfunction "VCC_16") (pintype "power_in"))
      (node (ref "IC9") (pin "3") (pinfunction "VO_3") (pintype "passive"))
      (node (ref "L9") (pin "2") (pinfunction "2_2") (pintype "passive"))
      (node (ref "PROG") (pin "3") (pinfunction "3_3") (pintype "passive"))
      (node (ref "TAP") (pin "11") (pinfunction "11_11") (pintype "passive"))
      (node (ref "TAP") (pin "12") (pinfunction "12_12") (pintype "passive"))
      (node (ref "TAP") (pin "13") (pinfunction "13_13") (pintype "passive"))
      (node (ref "TAP") (pin "14") (pinfunction "14_14") (pintype "passive"))
    )
    (net (code "2") (name "+12V") (class "Default")
      (node (ref "C62") (pin "1") (pinfunction "1_1") (pintype "passive"))
      (node (ref "C67") (pin "1") (pinfunction "1_1") (pintype "passive"))
      (node (ref "IC11") (pin "1") (pinfunction "PVCCL_1") (pintype "input"))
      (node (ref "IC11") (pin "10") (pinfunction "PVCCR_10") (pintype "input"))
      (node (ref "IC11") (pin "12") (pinfunction "PVCCR_12") (pintype "input"))
      (node (ref "IC11") (pin "3") (pinfunction "PVCCL_3") (pintype "input"))
      (node (ref "R54") (pin "2") (pinfunction "2_2") (pintype "passive"))
      (node (ref "SJ3") (pin "2") (pinfunction "2_2") (pintype "passive"))
    )
    (net (code "3") (name "+24V") (class "Default")
      (node (ref "42V") (pin "2") (pinfunction "S_2") (pintype "passive"))
      (node (ref "D12") (pin "1") (pinfunction "C_1") (pintype "passive"))
      (node (ref "D13") (pin "1") (pinfunction "C_1") (pintype "passive"))
      (node (ref "F2") (pin "1") (pinfunction "1_1") (pintype "passive"))
    )
    (net (code "4") (name "-24V") (class "Default")
      (node (ref "42V") (pin "1") (pinfunction "S_1") (pintype "passive"))
      (node (ref "DSUB1") (pin "9") (pinfunction "M_9") (pintype "passive"))
      (node (ref "L8") (pin "1") (pinfunction "1_1") (pintype "passive"))
      (node (ref "RJ2") (pin "7") (pinfunction "7_7") (pintype "passive"))
    )
    (net (code "5") (name "12V_TAP") (class "Default")
      (node (ref "C23") (pin "1") (pinfunction "1_1") (pintype "passive"))
      (node (ref "C24") (pin "1") (pinfunction "1_1") (pintype "passive"))
      (node (ref "C50") (pin "+") (pinfunction "+_+") (pintype "passive"))
      (node (ref "C51") (pin "1") (pinfunction "1_1") (pintype "passive"))
      (node (ref "D16") (pin "A") (pinfunction "A_A") (pintype "passive"))
      (node (ref "DIGIT") (pin "13") (pinfunction "13_13") (pintype "passive"))
      (node (ref "DIGIT") (pin "14") (pinfunction "14_14") (pintype "passive"))
      (node (ref "IC9") (pin "1") (pinfunction "VI_1") (pintype "input"))
      (node (ref "R49") (pin "2") (pinfunction "2_2") (pintype "passive"))
      (node (ref "R50") (pin "2") (pinfunction "2_2") (pintype "passive"))
      (node (ref "R51") (pin "2") (pinfunction "2_2") (pintype "passive"))
      (node (ref "SD2") (pin "OUT+") (pinfunction "OUT+_OUT+") (pintype "bidirectional"))
      (node (ref "SJ3") (pin "1") (pinfunction "1_1") (pintype "passive"))
    )
    (net (code "6") (name "AGND") (class "Default")
      (node (ref "C1") (pin "-") (pinfunction "-_-") (pintype "passive"))
      (node (ref "C10") (pin "2") (pinfunction "2_2") (pintype "passive"))
      (node (ref "C17") (pin "2") (pinfunction "2_2") (pintype "passive"))
      (node (ref "C26") (pin "2") (pinfunction "2_2") (pintype "passive"))
      (node (ref "C27") (pin "1") (pinfunction "1_1") (pintype "passive"))
      (node (ref "C50") (pin "-") (pinfunction "-_-") (pintype "passive"))
      (node (ref "C51") (pin "2") (pinfunction "2_2") (pintype "passive"))
      (node (ref "C54") (pin "+") (pinfunction "+_+") (pintype "passive"))
      (node (ref "C55") (pin "1") (pinfunction "1_1") (pintype "passive"))
      (node (ref "C56") (pin "2") (pinfunction "2_2") (pintype "passive"))
      (node (ref "C57") (pin "-") (pinfunction "-_-") (pintype "passive"))
      (node (ref "C58") (pin "2") (pinfunction "2_2") (pintype "passive"))
      (node (ref "C59") (pin "2") (pinfunction "2_2") (pintype "passive"))
      (node (ref "C62") (pin "2") (pinfunction "2_2") (pintype "passive"))
      (node (ref "C63") (pin "2") (pinfunction "2_2") (pintype "passive"))
      (node (ref "C64") (pin "1") (pinfunction "1_1") (pintype "passive"))
      (node (ref "C67") (pin "2") (pinfunction "2_2") (pintype "passive"))
      (node (ref "C7") (pin "2") (pinfunction "2_2") (pintype "passive"))
      (node (ref "C70") (pin "1") (pinfunction "1_1") (pintype "passive"))
      (node (ref "D15") (pin "C") (pinfunction "C_C") (pintype "passive"))
      (node (ref "D18") (pin "C") (pinfunction "C_C") (pintype "passive"))
      (node (ref "DSUB1") (pin "1") (pinfunction "M_1") (pintype "passive"))
      (node (ref "FENYELL") (pin "1") (pinfunction "1_1") (pintype "passive"))
      (node (ref "F_LED") (pin "1") (pinfunction "1_1") (pintype "passive"))
      (node (ref "HP_KI") (pin "1") (pinfunction "S_1") (pintype "passive"))
      (node (ref "IC11") (pin "13") (pinfunction "PGNDR_13") (pintype "input"))
      (node (ref "IC11") (pin "14") (pinfunction "PGNDR_14") (pintype "input"))
      (node (ref "IC11") (pin "17") (pinfunction "GAIN1_17") (pintype "input"))
      (node (ref "IC11") (pin "23") (pinfunction "PGNDL_23") (pintype "input"))
      (node (ref "IC11") (pin "24") (pinfunction "PGNDL_24") (pintype "input"))
      (node (ref "IC11") (pin "8") (pinfunction "AGND_8") (pintype "input"))
      (node (ref "IC11") (pin "9") (pinfunction "AGND_9") (pintype "input"))
      (node (ref "IC3") (pin "1") (pinfunction "Y1_1") (pintype "bidirectional"))
      (node (ref "IC3") (pin "8") (pinfunction "GND_8") (pintype "power_in"))
      (node (ref "IC4") (pin "5") (pinfunction "+IN_5") (pintype "input"))
      (node (ref "LAMPA") (pin "1") (pinfunction "S_1") (pintype "passive"))
      (node (ref "MIC") (pin "2") (pinfunction "S_2") (pintype "passive"))
      (node (ref "MIC") (pin "3") (pinfunction "S_3") (pintype "passive"))
      (node (ref "MIC") (pin "4") (pinfunction "S_4") (pintype "passive"))
      (node (ref "POTI") (pin "5") (pinfunction "5_5") (pintype "passive"))
      (node (ref "POTI") (pin "6") (pinfunction "6_6") (pintype "passive"))
      (node (ref "Q1") (pin "2") (pinfunction "S_2") (pintype "passive"))
      (node (ref "Q3") (pin "2") (pinfunction "S_2") (pintype "passive"))
      (node (ref "R14") (pin "1") (pinfunction "1_1") (pintype "passive"))
      (node (ref "R15") (pin "1") (pinfunction "1_1") (pintype "passive"))
      (node (ref "R16") (pin "1") (pinfunction "1_1") (pintype "passive"))
      (node (ref "R2") (pin "1") (pinfunction "1_1") (pintype "passive"))
      (node (ref "R20") (pin "1") (pinfunction "1_1") (pintype "passive"))
      (node (ref "R22") (pin "1") (pinfunction "1_1") (pintype "passive"))
      (node (ref "R24") (pin "1") (pinfunction "1_1") (pintype "passive"))
      (node (ref "R28") (pin "1") (pinfunction "1_1") (pintype "passive"))
      (node (ref "R3") (pin "1") (pinfunction "1_1") (pintype "passive"))
      (node (ref "R30") (pin "1") (pinfunction "1_1") (pintype "passive"))
      (node (ref "R31") (pin "1") (pinfunction "1_1") (pintype "passive"))
      (node (ref "R5") (pin "1") (pinfunction "1_1") (pintype "passive"))
      (node (ref "R52") (pin "1") (pinfunction "1_1") (pintype "passive"))
      (node (ref "R53") (pin "2") (pinfunction "2_2") (pintype "passive"))
      (node (ref "R56") (pin "2") (pinfunction "2_2") (pintype "passive"))
      (node (ref "R9") (pin "1") (pinfunction "1_1") (pintype "passive"))
      (node (ref "RJ2") (pin "S1") (pinfunction "S_S1") (pintype "passive"))
      (node (ref "RJ2") (pin "S2") (pinfunction "S_S2") (pintype "passive"))
      (node (ref "SD2") (pin "COMMON") (pinfunction "GND_COMMON") (pintype "bidirectional"))
      (node (ref "SJ2") (pin "3") (pinfunction "3_3") (pintype "passive"))
      (node (ref "SJ6") (pin "1") (pinfunction "1_1") (pintype "passive"))
      (node (ref "SJ7") (pin "3") (pinfunction "3_3") (pintype "passive"))
      (node (ref "SJ8") (pin "2") (pinfunction "2_2") (pintype "passive"))
      (node (ref "SP_KI") (pin "1") (pinfunction "S_1") (pintype "passive"))
      (node (ref "SP_KI") (pin "3") (pinfunction "S_3") (pintype "passive"))
    )
    (net (code "7") (name "CANH") (class "Default")
      (node (ref "DSUB1") (pin "7") (pinfunction "M_7") (pintype "passive"))
      (node (ref "PROG") (pin "6") (pinfunction "6_6") (pintype "passive"))
      (node (ref "RJ2") (pin "5") (pinfunction "5_5") (pintype "passive"))
      (node (ref "TAP") (pin "10") (pinfunction "10_10") (pintype "passive"))
      (node (ref "TAP") (pin "9") (pinfunction "9_9") (pintype "passive"))
    )
    (net (code "8") (name "CANL") (class "Default")
      (node (ref "DSUB1") (pin "6") (pinfunction "M_6") (pintype "passive"))
      (node (ref "R36") (pin "1") (pinfunction "1_1") (pintype "passive"))
      (node (ref "R37") (pin "1") (pinfunction "1_1") (pintype "passive"))
      (node (ref "RJ2") (pin "4") (pinfunction "4_4") (pintype "passive"))
      (node (ref "TAP") (pin "7") (pinfunction "7_7") (pintype "passive"))
      (node (ref "TAP") (pin "8") (pinfunction "8_8") (pintype "passive"))
    )
    (net (code "9") (name "CLK") (class "Default")
      (node (ref "PROG") (pin "9") (pinfunction "9_9") (pintype "passive"))
      (node (ref "TAP") (pin "5") (pinfunction "5_5") (pintype "passive"))
      (node (ref "TAP") (pin "6") (pinfunction "6_6") (pintype "passive"))
    )
    (net (code "10") (name "CRM") (class "Default")
      (node (ref "DIGIT") (pin "3") (pinfunction "3_3") (pintype "passive"))
      (node (ref "DIGIT") (pin "4") (pinfunction "4_4") (pintype "passive"))
      (node (ref "IC3") (pin "9") (pinfunction "C_9") (pintype "input"))
    )
    (net (code "11") (name "CROSSMUTE_CS") (class "Default")
      (node (ref "IC3") (pin "3") (pinfunction "Z1_3") (pintype "bidirectional"))
      (node (ref "POTI") (pin "13") (pinfunction "13_13") (pintype "passive"))
    )
    (net (code "12") (name "CROSSMUTE_MAX") (class "Default")
      (node (ref "IC3") (pin "5") (pinfunction "Z0_5") (pintype "bidirectional"))
      (node (ref "JUMPER") (pin "6") (pinfunction "6_6") (pintype "passive"))
      (node (ref "POTI") (pin "14") (pinfunction "14_14") (pintype "passive"))
    )
    (net (code "13") (name "CSIP") (class "Default")
      (node (ref "D1") (pin "A") (pinfunction "A_A") (pintype "passive"))
      (node (ref "D2") (pin "C") (pinfunction "C_C") (pintype "passive"))
      (node (ref "DIGIT") (pin "1") (pinfunction "1_1") (pintype "passive"))
      (node (ref "DIGIT") (pin "2") (pinfunction "2_2") (pintype "passive"))
    )
    (net (code "14") (name "DAT") (class "Default")
      (node (ref "PROG") (pin "7") (pinfunction "7_7") (pintype "passive"))
      (node (ref "TAP") (pin "3") (pinfunction "3_3") (pintype "passive"))
      (node (ref "TAP") (pin "4") (pinfunction "4_4") (pintype "passive"))
    )
    (net (code "15") (name "DIN_MIC") (class "Default")
      (node (ref "C5") (pin "1") (pinfunction "1_1") (pintype "passive"))
      (node (ref "MIC") (pin "5") (pinfunction "S_5") (pintype "passive"))
      (node (ref "R5") (pin "2") (pinfunction "2_2") (pintype "passive"))
    )
    (net (code "16") (name "EL_MIC") (class "Default")
      (node (ref "C4") (pin "1") (pinfunction "1_1") (pintype "passive"))
      (node (ref "MIC") (pin "1") (pinfunction "S_1") (pintype "passive"))
      (node (ref "R4") (pin "1") (pinfunction "1_1") (pintype "passive"))
    )
    (net (code "17") (name "GAIN_CS") (class "Default")
      (node (ref "POTI") (pin "17") (pinfunction "17_17") (pintype "passive"))
      (node (ref "POTI") (pin "18") (pinfunction "18_18") (pintype "passive"))
      (node (ref "R12") (pin "2") (pinfunction "2_2") (pintype "passive"))
    )
    (net (code "18") (name "GAIN_MAX") (class "Default")
      (node (ref "POTI") (pin "15") (pinfunction "15_15") (pintype "passive"))
      (node (ref "POTI") (pin "16") (pinfunction "16_16") (pintype "passive"))
      (node (ref "R15") (pin "2") (pinfunction "2_2") (pintype "passive"))
    )
    (net (code "19") (name "GAIN_MIN") (class "Default")
      (node (ref "C11") (pin "2") (pinfunction "2_2") (pintype "passive"))
      (node (ref "C8") (pin "1") (pinfunction "1_1") (pintype "passive"))
      (node (ref "IC1") (pin "1") (pinfunction "OUT_1") (pintype "output"))
      (node (ref "POTI") (pin "19") (pinfunction "19_19") (pintype "passive"))
      (node (ref "POTI") (pin "20") (pinfunction "20_20") (pintype "passive"))
    )
    (net (code "20") (name "GND") (class "Default")
      (node (ref "C23") (pin "2") (pinfunction "2_2") (pintype "passive"))
      (node (ref "C24") (pin "2") (pinfunction "2_2") (pintype "passive"))
      (node (ref "C25") (pin "2") (pinfunction "2_2") (pintype "passive"))
      (node (ref "C52") (pin "2") (pinfunction "2_2") (pintype "passive"))
      (node (ref "C53") (pin "-") (pinfunction "-_-") (pintype "passive"))
      (node (ref "D14") (pin "2") (pinfunction "A_2") (pintype "passive"))
      (node (ref "IC9") (pin "2") (pinfunction "GND_2") (pintype "passive"))
      (node (ref "JP2") (pin "1") (pinfunction "1_1") (pintype "passive"))
      (node (ref "PROG") (pin "1") (pinfunction "1_1") (pintype "passive"))
      (node (ref "R48") (pin "1") (pinfunction "1_1") (pintype "passive"))
      (node (ref "SJ6") (pin "2") (pinfunction "2_2") (pintype "passive"))
      (node (ref "TAP") (pin "15") (pinfunction "15_15") (pintype "passive"))
      (node (ref "TAP") (pin "16") (pinfunction "16_16") (pintype "passive"))
      (node (ref "TAP") (pin "17") (pinfunction "17_17") (pintype "passive"))
      (node (ref "TAP") (pin "18") (pinfunction "18_18") (pintype "passive"))
      (node (ref "TAP") (pin "19") (pinfunction "19_19") (pintype "passive"))
      (node (ref "TAP") (pin "20") (pinfunction "20_20") (pintype "passive"))
    )
    (net (code "21") (name "HP") (class "Default")
      (node (ref "IC3") (pin "13") (pinfunction "X1_13") (pintype "bidirectional"))
      (node (ref "JUMPER") (pin "1") (pinfunction "1_1") (pintype "passive"))
      (node (ref "POTI") (pin "11") (pinfunction "11_11") (pintype "passive"))
      (node (ref "POTI") (pin "12") (pinfunction "12_12") (pintype "passive"))
    )
    (net (code "22") (name "HPOUT") (class "Default")
      (node (ref "C61") (pin "2") (pinfunction "2_2") (pintype "passive"))
      (node (ref "IC11") (pin "22") (pinfunction "LOUT_22") (pintype "output"))
      (node (ref "L11") (pin "1") (pinfunction "1_1") (pintype "passive"))
    )
    (net (code "23") (name "IN+") (class "Default")
      (node (ref "C2") (pin "1") (pinfunction "1_1") (pintype "passive"))
      (node (ref "DSUB1") (pin "2") (pinfunction "M_2") (pintype "passive"))
      (node (ref "R2") (pin "2") (pinfunction "2_2") (pintype "passive"))
      (node (ref "RJ2") (pin "2") (pinfunction "2_2") (pintype "passive"))
    )
    (net (code "24") (name "IN-") (class "Default")
      (node (ref "C3") (pin "1") (pinfunction "1_1") (pintype "passive"))
      (node (ref "DSUB1") (pin "3") (pinfunction "M_3") (pintype "passive"))
      (node (ref "R3") (pin "2") (pinfunction "2_2") (pintype "passive"))
      (node (ref "RJ2") (pin "1") (pinfunction "1_1") (pintype "passive"))
    )
    (net (code "25") (name "LAMPA_CS") (class "Default")
      (node (ref "POTI") (pin "2") (pinfunction "2_2") (pintype "passive"))
      (node (ref "T2") (pin "1") (pinfunction "B_1") (pintype "passive"))
    )
    (net (code "26") (name "LAMPA_MAX") (class "Default")
      (node (ref "D17") (pin "C") (pinfunction "C_C") (pintype "passive"))
      (node (ref "POTI") (pin "3") (pinfunction "3_3") (pintype "passive"))
      (node (ref "R48") (pin "2") (pinfunction "2_2") (pintype "passive"))
    )
    (net (code "27") (name "LAMPA_MIN") (class "Default")
      (node (ref "POTI") (pin "1") (pinfunction "1_1") (pintype "passive"))
      (node (ref "R49") (pin "1") (pinfunction "1_1") (pintype "passive"))
    )
    (net (code "28") (name "MH") (class "Default")
      (node (ref "DIGIT") (pin "7") (pinfunction "7_7") (pintype "passive"))
      (node (ref "DIGIT") (pin "8") (pinfunction "8_8") (pintype "passive"))
      (node (ref "IC3") (pin "11") (pinfunction "A_11") (pintype "input"))
    )
    (net (code "29") (name "MIC_MUTE") (class "Default")
      (node (ref "DIGIT") (pin "11") (pinfunction "11_11") (pintype "passive"))
      (node (ref "DIGIT") (pin "12") (pinfunction "12_12") (pintype "passive"))
      (node (ref "Q1") (pin "1") (pinfunction "G_1") (pintype "passive"))
    )
    (net (code "30") (name "MUTE") (class "Default")
      (node (ref "DIGIT") (pin "10") (pinfunction "10_10") (pintype "passive"))
      (node (ref "DIGIT") (pin "9") (pinfunction "9_9") (pintype "passive"))
      (node (ref "Q3") (pin "1") (pinfunction "G_1") (pintype "passive"))
    )
    (net (code "31") (name "N$49") (class "Default")
      (node (ref "IC3") (pin "14") (pinfunction "X_14") (pintype "bidirectional"))
      (node (ref "JUMPER") (pin "4") (pinfunction "4_4") (pintype "passive"))
      (node (ref "R30") (pin "2") (pinfunction "2_2") (pintype "passive"))
      (node (ref "SJ5") (pin "2") (pinfunction "2_2") (pintype "passive"))
    )
    (net (code "32") (name "N$50") (class "Default")
      (node (ref "IC3") (pin "15") (pinfunction "Y_15") (pintype "bidirectional"))
      (node (ref "R28") (pin "2") (pinfunction "2_2") (pintype "passive"))
      (node (ref "SJ4") (pin "2") (pinfunction "2_2") (pintype "passive"))
    )
    (net (code "33") (name "Net-(C1-Pad+)") (class "Default")
      (node (ref "C1") (pin "+") (pinfunction "+_+") (pintype "passive"))
      (node (ref "R1") (pin "1") (pinfunction "1_1") (pintype "passive"))
      (node (ref "R4") (pin "2") (pinfunction "2_2") (pintype "passive"))
    )
    (net (code "34") (name "Net-(C2-Pad2)") (class "Default")
      (node (ref "C2") (pin "2") (pinfunction "2_2") (pintype "passive"))
      (node (ref "R6") (pin "1") (pinfunction "1_1") (pintype "passive"))
    )
    (net (code "35") (name "Net-(C3-Pad2)") (class "Default")
      (node (ref "C3") (pin "2") (pinfunction "2_2") (pintype "passive"))
      (node (ref "R7") (pin "1") (pinfunction "1_1") (pintype "passive"))
    )
    (net (code "36") (name "Net-(C4-Pad2)") (class "Default")
      (node (ref "C4") (pin "2") (pinfunction "2_2") (pintype "passive"))
      (node (ref "R10") (pin "1") (pinfunction "1_1") (pintype "passive"))
    )
    (net (code "37") (name "Net-(C5-Pad2)") (class "Default")
      (node (ref "C5") (pin "2") (pinfunction "2_2") (pintype "passive"))
      (node (ref "R11") (pin "1") (pinfunction "1_1") (pintype "passive"))
      (node (ref "R8") (pin "2") (pinfunction "2_2") (pintype "passive"))
    )
    (net (code "38") (name "Net-(C6-Pad2)") (class "Default")
      (node (ref "C6") (pin "2") (pinfunction "2_2") (pintype "passive"))
      (node (ref "R8") (pin "1") (pinfunction "1_1") (pintype "passive"))
    )
    (net (code "39") (name "Net-(C11-Pad1)") (class "Default")
      (node (ref "C11") (pin "1") (pinfunction "1_1") (pintype "passive"))
      (node (ref "R16") (pin "2") (pinfunction "2_2") (pintype "passive"))
      (node (ref "R18") (pin "1") (pinfunction "1_1") (pintype "passive"))
    )
    (net (code "40") (name "Net-(C12-Pad1)") (class "Default")
      (node (ref "C12") (pin "1") (pinfunction "1_1") (pintype "passive"))
      (node (ref "R19") (pin "1") (pinfunction "1_1") (pintype "passive"))
    )
    (net (code "41") (name "Net-(C12-Pad2)") (class "Default")
      (node (ref "C12") (pin "2") (pinfunction "2_2") (pintype "passive"))
      (node (ref "D1") (pin "C") (pinfunction "C_C") (pintype "passive"))
      (node (ref "D2") (pin "A") (pinfunction "A_A") (pintype "passive"))
    )
    (net (code "42") (name "Net-(C13-Pad1)") (class "Default")
      (node (ref "C13") (pin "1") (pinfunction "1_1") (pintype "passive"))
      (node (ref "R17") (pin "2") (pinfunction "2_2") (pintype "passive"))
      (node (ref "R19") (pin "2") (pinfunction "2_2") (pintype "passive"))
    )
    (net (code "43") (name "Net-(C17-Pad1)") (class "Default")
      (node (ref "C17") (pin "1") (pinfunction "1_1") (pintype "passive"))
      (node (ref "D3") (pin "C") (pinfunction "C_C") (pintype "passive"))
      (node (ref "R27") (pin "2") (pinfunction "2_2") (pintype "passive"))
    )
    (net (code "44") (name "Net-(C20-Pad2)") (class "Default")
      (node (ref "C20") (pin "2") (pinfunction "2_2") (pintype "passive"))
      (node (ref "R34") (pin "1") (pinfunction "1_1") (pintype "passive"))
    )
    (net (code "45") (name "Net-(C21-Pad2)") (class "Default")
      (node (ref "C21") (pin "2") (pinfunction "2_2") (pintype "passive"))
      (node (ref "R35") (pin "1") (pinfunction "1_1") (pintype "passive"))
    )
    (net (code "46") (name "Net-(C54-Pad-)") (class "Default")
      (node (ref "C54") (pin "-") (pinfunction "-_-") (pintype "passive"))
      (node (ref "C55") (pin "2") (pinfunction "2_2") (pintype "passive"))
      (node (ref "D15") (pin "A") (pinfunction "A_A") (pintype "passive"))
      (node (ref "D19") (pin "A") (pinfunction "A_A") (pintype "passive"))
      (node (ref "SJ1") (pin "2") (pinfunction "2_2") (pintype "passive"))
      (node (ref "SJ7") (pin "1") (pinfunction "1_1") (pintype "passive"))
    )
    (net (code "47") (name "Net-(C63-Pad1)") (class "Default")
      (node (ref "C63") (pin "1") (pinfunction "1_1") (pintype "passive"))
      (node (ref "C65") (pin "+") (pinfunction "+_+") (pintype "passive"))
      (node (ref "L10") (pin "2") (pinfunction "2_2") (pintype "passive"))
      (node (ref "R52") (pin "2") (pinfunction "2_2") (pintype "passive"))
    )
    (net (code "48") (name "Net-(C64-Pad2)") (class "Default")
      (node (ref "C64") (pin "2") (pinfunction "2_2") (pintype "passive"))
      (node (ref "L11") (pin "2") (pinfunction "2_2") (pintype "passive"))
      (node (ref "L12") (pin "1") (pinfunction "1_1") (pintype "passive"))
      (node (ref "R53") (pin "1") (pinfunction "1_1") (pintype "passive"))
    )
    (net (code "49") (name "Net-(C66-Pad+)") (class "Default")
      (node (ref "C66") (pin "+") (pinfunction "+_+") (pintype "passive"))
      (node (ref "C70") (pin "2") (pinfunction "2_2") (pintype "passive"))
      (node (ref "L12") (pin "2") (pinfunction "2_2") (pintype "passive"))
    )
    (net (code "50") (name "Net-(C68-Pad1)") (class "Default")
      (node (ref "C68") (pin "1") (pinfunction "1_1") (pintype "passive"))
      (node (ref "SJ4") (pin "1") (pinfunction "1_1") (pintype "passive"))
    )
    (net (code "51") (name "Net-(C69-Pad1)") (class "Default")
      (node (ref "C69") (pin "1") (pinfunction "1_1") (pintype "passive"))
      (node (ref "SJ5") (pin "1") (pinfunction "1_1") (pintype "passive"))
    )
    (net (code "52") (name "Net-(C71-Pad1)") (class "Default")
      (node (ref "C71") (pin "1") (pinfunction "1_1") (pintype "passive"))
      (node (ref "R55") (pin "2") (pinfunction "2_2") (pintype "passive"))
      (node (ref "SD2") (pin "HACK") (pinfunction "HACK_HACK") (pintype "bidirectional"))
    )
    (net (code "53") (name "Net-(D3-PadA)") (class "Default")
      (node (ref "D3") (pin "A") (pinfunction "A_A") (pintype "passive"))
      (node (ref "R26") (pin "2") (pinfunction "2_2") (pintype "passive"))
    )
    (net (code "54") (name "Net-(D12-A)") (class "Default")
      (node (ref "D12") (pin "2") (pinfunction "A_2") (pintype "passive"))
      (node (ref "RJ2") (pin "8") (pinfunction "8_8") (pintype "passive"))
    )
    (net (code "55") (name "Net-(D13-A)") (class "Default")
      (node (ref "D13") (pin "2") (pinfunction "A_2") (pintype "passive"))
      (node (ref "DSUB1") (pin "8") (pinfunction "M_8") (pintype "passive"))
    )
    (net (code "56") (name "Net-(D14-C)") (class "Default")
      (node (ref "D14") (pin "1") (pinfunction "C_1") (pintype "passive"))
      (node (ref "JP1") (pin "1") (pinfunction "1_1") (pintype "passive"))
      (node (ref "L9") (pin "1") (pinfunction "1_1") (pintype "passive"))
    )
    (net (code "57") (name "Net-(D16-PadC)") (class "Default")
      (node (ref "D16") (pin "C") (pinfunction "C_C") (pintype "passive"))
      (node (ref "D17") (pin "A") (pinfunction "A_A") (pintype "passive"))
    )
    (net (code "58") (name "Net-(D18-PadA)") (class "Default")
      (node (ref "D18") (pin "A") (pinfunction "A_A") (pintype "passive"))
      (node (ref "D19") (pin "C") (pinfunction "C_C") (pintype "passive"))
      (node (ref "R55") (pin "1") (pinfunction "1_1") (pintype "passive"))
    )
    (net (code "59") (name "Net-(F2-Pad2)") (class "Default")
      (node (ref "F2") (pin "2") (pinfunction "2_2") (pintype "passive"))
      (node (ref "L7") (pin "1") (pinfunction "1_1") (pintype "passive"))
    )
    (net (code "60") (name "Net-(F_LED-Pad2)") (class "Default")
      (node (ref "F_LED") (pin "2") (pinfunction "2_2") (pintype "passive"))
      (node (ref "R27") (pin "1") (pinfunction "1_1") (pintype "passive"))
    )
    (net (code "61") (name "Net-(GAIN-PadE)") (class "Default")
      (node (ref "GAIN") (pin "E") (pinfunction "E_E") (pintype "passive"))
      (node (ref "R46") (pin "1") (pinfunction "1_1") (pintype "passive"))
    )
    (net (code "62") (name "Net-(HP_KIB-S)") (class "Default")
      (node (ref "C66") (pin "-") (pinfunction "-_-") (pintype "passive"))
      (node (ref "HP_KI") (pin "2") (pinfunction "S_2") (pintype "passive"))
      (node (ref "R56") (pin "1") (pinfunction "1_1") (pintype "passive"))
    )
    (net (code "63") (name "Net-(IC1A-+IN)") (class "Default")
      (node (ref "C10") (pin "1") (pinfunction "1_1") (pintype "passive"))
      (node (ref "IC1") (pin "3") (pinfunction "+IN_3") (pintype "input"))
      (node (ref "R10") (pin "2") (pinfunction "2_2") (pintype "passive"))
      (node (ref "R14") (pin "2") (pinfunction "2_2") (pintype "passive"))
    )
    (net (code "64") (name "Net-(IC1A--IN)") (class "Default")
      (node (ref "C6") (pin "1") (pinfunction "1_1") (pintype "passive"))
      (node (ref "C8") (pin "2") (pinfunction "2_2") (pintype "passive"))
      (node (ref "IC1") (pin "2") (pinfunction "-IN_2") (pintype "input"))
      (node (ref "R11") (pin "2") (pinfunction "2_2") (pintype "passive"))
      (node (ref "R12") (pin "1") (pinfunction "1_1") (pintype "passive"))
    )
    (net (code "65") (name "Net-(IC1B-+IN)") (class "Default")
      (node (ref "FENYELL") (pin "2") (pinfunction "2_2") (pintype "passive"))
      (node (ref "IC1") (pin "5") (pinfunction "+IN_5") (pintype "input"))
      (node (ref "Q1") (pin "3") (pinfunction "D_3") (pintype "passive"))
      (node (ref "R18") (pin "2") (pinfunction "2_2") (pintype "passive"))
    )
    (net (code "66") (name "Net-(IC1B--IN)") (class "Default")
      (node (ref "C14") (pin "2") (pinfunction "2_2") (pintype "passive"))
      (node (ref "IC1") (pin "6") (pinfunction "-IN_6") (pintype "input"))
      (node (ref "R20") (pin "2") (pinfunction "2_2") (pintype "passive"))
      (node (ref "R21") (pin "1") (pinfunction "1_1") (pintype "passive"))
    )
    (net (code "67") (name "Net-(IC1B-OUT)") (class "Default")
      (node (ref "C14") (pin "1") (pinfunction "1_1") (pintype "passive"))
      (node (ref "C15") (pin "2") (pinfunction "2_2") (pintype "passive"))
      (node (ref "IC1") (pin "7") (pinfunction "OUT_7") (pintype "output"))
      (node (ref "IC2") (pin "3") (pinfunction "+IN_3") (pintype "input"))
      (node (ref "R21") (pin "2") (pinfunction "2_2") (pintype "passive"))
    )
    (net (code "68") (name "Net-(IC2A--IN)") (class "Default")
      (node (ref "C16") (pin "2") (pinfunction "2_2") (pintype "passive"))
      (node (ref "IC2") (pin "2") (pinfunction "-IN_2") (pintype "input"))
      (node (ref "R22") (pin "2") (pinfunction "2_2") (pintype "passive"))
      (node (ref "R23") (pin "1") (pinfunction "1_1") (pintype "passive"))
    )
    (net (code "69") (name "Net-(IC2A-OUT)") (class "Default")
      (node (ref "C16") (pin "1") (pinfunction "1_1") (pintype "passive"))
      (node (ref "IC2") (pin "1") (pinfunction "OUT_1") (pintype "output"))
      (node (ref "LED1") (pin "K") (pinfunction "C_K") (pintype "passive"))
      (node (ref "R25") (pin "2") (pinfunction "2_2") (pintype "passive"))
      (node (ref "R26") (pin "1") (pinfunction "1_1") (pintype "passive"))
    )
    (net (code "70") (name "Net-(IC2B-+IN)") (class "Default")
      (node (ref "C7") (pin "1") (pinfunction "1_1") (pintype "passive"))
      (node (ref "IC2") (pin "5") (pinfunction "+IN_5") (pintype "input"))
      (node (ref "R6") (pin "2") (pinfunction "2_2") (pintype "passive"))
      (node (ref "R9") (pin "2") (pinfunction "2_2") (pintype "passive"))
    )
    (net (code "71") (name "Net-(IC2B--IN)") (class "Default")
      (node (ref "C9") (pin "2") (pinfunction "2_2") (pintype "passive"))
      (node (ref "IC2") (pin "6") (pinfunction "-IN_6") (pintype "input"))
      (node (ref "R13") (pin "1") (pinfunction "1_1") (pintype "passive"))
      (node (ref "R7") (pin "2") (pinfunction "2_2") (pintype "passive"))
    )
    (net (code "72") (name "Net-(IC2B-OUT)") (class "Default")
      (node (ref "C9") (pin "1") (pinfunction "1_1") (pintype "passive"))
      (node (ref "IC2") (pin "7") (pinfunction "OUT_7") (pintype "output"))
      (node (ref "R13") (pin "2") (pinfunction "2_2") (pintype "passive"))
      (node (ref "R17") (pin "1") (pinfunction "1_1") (pintype "passive"))
    )
    (net (code "73") (name "Net-(IC3A-INH)") (class "Default")
      (node (ref "IC3") (pin "6") (pinfunction "INH_6") (pintype "input"))
      (node (ref "Q3") (pin "3") (pinfunction "D_3") (pintype "passive"))
      (node (ref "R54") (pin "1") (pinfunction "1_1") (pintype "passive"))
    )
    (net (code "74") (name "Net-(IC3A-Y0)") (class "Default")
      (node (ref "IC3") (pin "2") (pinfunction "Y0_2") (pintype "bidirectional"))
      (node (ref "IC3") (pin "4") (pinfunction "Z_4") (pintype "bidirectional"))
    )
    (net (code "75") (name "Net-(IC4A-+IN)") (class "Default")
      (node (ref "C15") (pin "1") (pinfunction "1_1") (pintype "passive"))
      (node (ref "IC4") (pin "3") (pinfunction "+IN_3") (pintype "input"))
      (node (ref "R24") (pin "2") (pinfunction "2_2") (pintype "passive"))
      (node (ref "R29") (pin "2") (pinfunction "2_2") (pintype "passive"))
    )
    (net (code "76") (name "Net-(IC4A--IN)") (class "Default")
      (node (ref "C18") (pin "2") (pinfunction "2_2") (pintype "passive"))
      (node (ref "IC4") (pin "2") (pinfunction "-IN_2") (pintype "input"))
      (node (ref "R31") (pin "2") (pinfunction "2_2") (pintype "passive"))
      (node (ref "R32") (pin "1") (pinfunction "1_1") (pintype "passive"))
    )
    (net (code "77") (name "Net-(IC4A-OUT)") (class "Default")
      (node (ref "C18") (pin "1") (pinfunction "1_1") (pintype "passive"))
      (node (ref "C20") (pin "1") (pinfunction "1_1") (pintype "passive"))
      (node (ref "IC4") (pin "1") (pinfunction "OUT_1") (pintype "output"))
      (node (ref "R32") (pin "2") (pinfunction "2_2") (pintype "passive"))
    )
    (net (code "78") (name "Net-(IC4B--IN)") (class "Default")
      (node (ref "C19") (pin "2") (pinfunction "2_2") (pintype "passive"))
      (node (ref "IC4") (pin "6") (pinfunction "-IN_6") (pintype "input"))
      (node (ref "R29") (pin "1") (pinfunction "1_1") (pintype "passive"))
      (node (ref "R33") (pin "1") (pinfunction "1_1") (pintype "passive"))
    )
    (net (code "79") (name "Net-(IC4B-OUT)") (class "Default")
      (node (ref "C19") (pin "1") (pinfunction "1_1") (pintype "passive"))
      (node (ref "C21") (pin "1") (pinfunction "1_1") (pintype "passive"))
      (node (ref "IC4") (pin "7") (pinfunction "OUT_7") (pintype "output"))
      (node (ref "R33") (pin "2") (pinfunction "2_2") (pintype "passive"))
    )
    (net (code "80") (name "Net-(IC11-BSL)") (class "Default")
      (node (ref "C61") (pin "1") (pinfunction "1_1") (pintype "passive"))
      (node (ref "IC11") (pin "21") (pinfunction "BSL_21") (pintype "passive"))
    )
    (net (code "81") (name "Net-(IC11-BSR)") (class "Default")
      (node (ref "C60") (pin "1") (pinfunction "1_1") (pintype "passive"))
      (node (ref "IC11") (pin "16") (pinfunction "BSR_16") (pintype "passive"))
    )
    (net (code "82") (name "Net-(IC11-BYPASS)") (class "Default")
      (node (ref "C56") (pin "1") (pinfunction "1_1") (pintype "passive"))
      (node (ref "IC11") (pin "7") (pinfunction "BYPASS_7") (pintype "input"))
    )
    (net (code "83") (name "Net-(IC11-GAIN0)") (class "Default")
      (node (ref "IC11") (pin "18") (pinfunction "GAIN0_18") (pintype "input"))
      (node (ref "SJ2") (pin "2") (pinfunction "2_2") (pintype "passive"))
    )
    (net (code "84") (name "Net-(IC11-LIN)") (class "Default")
      (node (ref "C69") (pin "2") (pinfunction "2_2") (pintype "passive"))
      (node (ref "IC11") (pin "5") (pinfunction "LIN_5") (pintype "input"))
    )
    (net (code "85") (name "Net-(IC11-MUTE)") (class "Default")
      (node (ref "IC11") (pin "4") (pinfunction "MUTE_4") (pintype "input"))
      (node (ref "SJ8") (pin "1") (pinfunction "1_1") (pintype "passive"))
    )
    (net (code "86") (name "Net-(IC11-RIN)") (class "Default")
      (node (ref "C68") (pin "2") (pinfunction "2_2") (pintype "passive"))
      (node (ref "IC11") (pin "6") (pinfunction "RIN_6") (pintype "input"))
    )
    (net (code "87") (name "Net-(IC11-VCLAMP)") (class "Default")
      (node (ref "C59") (pin "1") (pinfunction "1_1") (pintype "passive"))
      (node (ref "IC11") (pin "11") (pinfunction "VCLAMP_11") (pintype "input"))
    )
    (net (code "88") (name "Net-(J2A-S)") (class "Default")
      (node (ref "EXT1") (pin "E") (pinfunction "E_E") (pintype "passive"))
      (node (ref "J2") (pin "1") (pinfunction "S_1") (pintype "passive"))
    )
    (net (code "89") (name "Net-(J2B-S)") (class "Default")
      (node (ref "EXT1") (pin "S") (pinfunction "S_S") (pintype "passive"))
      (node (ref "J2") (pin "2") (pinfunction "S_2") (pintype "passive"))
    )
    (net (code "90") (name "Net-(J2C-S)") (class "Default")
      (node (ref "EXT1") (pin "A") (pinfunction "A_A") (pintype "passive"))
      (node (ref "J2") (pin "3") (pinfunction "S_3") (pintype "passive"))
    )
    (net (code "91") (name "Net-(J3A-S)") (class "Default")
      (node (ref "EXT2") (pin "E") (pinfunction "E_E") (pintype "passive"))
      (node (ref "J3") (pin "1") (pinfunction "S_1") (pintype "passive"))
    )
    (net (code "92") (name "Net-(J3B-S)") (class "Default")
      (node (ref "EXT2") (pin "S") (pinfunction "S_S") (pintype "passive"))
      (node (ref "J3") (pin "2") (pinfunction "S_2") (pintype "passive"))
    )
    (net (code "93") (name "Net-(J3C-S)") (class "Default")
      (node (ref "EXT2") (pin "A") (pinfunction "A_A") (pintype "passive"))
      (node (ref "J3") (pin "3") (pinfunction "S_3") (pintype "passive"))
    )
    (net (code "94") (name "Net-(LAMPAB-S)") (class "Default")
      (node (ref "LAMPA") (pin "2") (pinfunction "S_2") (pintype "passive"))
      (node (ref "T2") (pin "2") (pinfunction "C_2") (pintype "passive"))
    )
    (net (code "95") (name "Net-(LED1-PadA)") (class "Default")
      (node (ref "LED1") (pin "A") (pinfunction "A_A") (pintype "passive"))
      (node (ref "R23") (pin "2") (pinfunction "2_2") (pintype "passive"))
      (node (ref "R25") (pin "1") (pinfunction "1_1") (pintype "passive"))
    )
    (net (code "96") (name "Net-(PROG-Pad4)") (class "Default")
      (node (ref "PROG") (pin "4") (pinfunction "4_4") (pintype "passive"))
      (node (ref "R36") (pin "2") (pinfunction "2_2") (pintype "passive"))
    )
    (net (code "97") (name "Net-(PROG-Pad8)") (class "Default")
      (node (ref "PROG") (pin "8") (pinfunction "8_8") (pintype "passive"))
      (node (ref "R37") (pin "2") (pinfunction "2_2") (pintype "passive"))
    )
    (net (code "98") (name "Net-(SD2-CTRL)") (class "Default")
      (node (ref "C48") (pin "1") (pinfunction "1_1") (pintype "passive"))
      (node (ref "C49") (pin "+") (pinfunction "+_+") (pintype "passive"))
      (node (ref "R47") (pin "2") (pinfunction "2_2") (pintype "passive"))
      (node (ref "SD2") (pin "CONTROL") (pinfunction "CTRL_CONTROL") (pintype "bidirectional"))
    )
    (net (code "99") (name "Net-(SD2-IN+)") (class "Default")
      (node (ref "C22") (pin "+") (pinfunction "+_+") (pintype "passive"))
      (node (ref "C47") (pin "+") (pinfunction "+_+") (pintype "passive"))
      (node (ref "L7") (pin "2") (pinfunction "2_2") (pintype "passive"))
      (node (ref "SD2") (pin "INPUT+") (pinfunction "IN+_INPUT+") (pintype "bidirectional"))
    )
    (net (code "100") (name "Net-(SD2-IN-)") (class "Default")
      (node (ref "C22") (pin "-") (pinfunction "-_-") (pintype "passive"))
      (node (ref "C47") (pin "-") (pinfunction "-_-") (pintype "passive"))
      (node (ref "C48") (pin "2") (pinfunction "2_2") (pintype "passive"))
      (node (ref "C49") (pin "-") (pinfunction "-_-") (pintype "passive"))
      (node (ref "L8") (pin "2") (pinfunction "2_2") (pintype "passive"))
      (node (ref "R47") (pin "1") (pinfunction "1_1") (pintype "passive"))
      (node (ref "SD2") (pin "INPUT-") (pinfunction "IN-_INPUT-") (pintype "bidirectional"))
    )
    (net (code "101") (name "Net-(SD2-PadOUT-)") (class "Default")
      (node (ref "SD2") (pin "OUT-") (pinfunction "OUT-_OUT-") (pintype "bidirectional"))
      (node (ref "SJ7") (pin "2") (pinfunction "2_2") (pintype "passive"))
    )
    (net (code "102") (name "Net-(SP_KIB-S)") (class "Default")
      (node (ref "C65") (pin "-") (pinfunction "-_-") (pintype "passive"))
      (node (ref "SP_KI") (pin "2") (pinfunction "S_2") (pintype "passive"))
    )
    (net (code "103") (name "Net-(SV5-1)") (class "Default")
      (node (ref "LAMP") (pin "S") (pinfunction "S_S") (pintype "passive"))
      (node (ref "SV5") (pin "1A") (pinfunction "1_1A") (pintype "passive"))
    )
    (net (code "104") (name "Net-(SV5-2)") (class "Default")
      (node (ref "LAMP") (pin "A") (pinfunction "A_A") (pintype "passive"))
      (node (ref "SV5") (pin "1B") (pinfunction "2_1B") (pintype "passive"))
    )
    (net (code "105") (name "Net-(SV5-4)") (class "Default")
      (node (ref "LAMP") (pin "E") (pinfunction "E_E") (pintype "passive"))
      (node (ref "SV5") (pin "2B") (pinfunction "4_2B") (pintype "passive"))
    )
    (net (code "106") (name "Net-(SV5-5)") (class "Default")
      (node (ref "CRM") (pin "A") (pinfunction "A_A") (pintype "passive"))
      (node (ref "HP") (pin "A") (pinfunction "A_A") (pintype "passive"))
      (node (ref "SP") (pin "A") (pinfunction "A_A") (pintype "passive"))
      (node (ref "SV5") (pin "3A") (pinfunction "5_3A") (pintype "passive"))
      (node (ref "SV5") (pin "3B") (pinfunction "6_3B") (pintype "passive"))
    )
    (net (code "107") (name "Net-(SV5-7)") (class "Default")
      (node (ref "HP") (pin "E") (pinfunction "E_E") (pintype "passive"))
      (node (ref "SP") (pin "E") (pinfunction "E_E") (pintype "passive"))
      (node (ref "SV5") (pin "4A") (pinfunction "7_4A") (pintype "passive"))
      (node (ref "SV5") (pin "4B") (pinfunction "8_4B") (pintype "passive"))
    )
    (net (code "108") (name "Net-(SV5-10)") (class "Default")
      (node (ref "SP") (pin "S") (pinfunction "S_S") (pintype "passive"))
      (node (ref "SV5") (pin "5A") (pinfunction "9_5A") (pintype "passive"))
      (node (ref "SV5") (pin "5B") (pinfunction "10_5B") (pintype "passive"))
    )
    (net (code "109") (name "Net-(SV5-11)") (class "Default")
      (node (ref "HP") (pin "S") (pinfunction "S_S") (pintype "passive"))
      (node (ref "SV5") (pin "6A") (pinfunction "11_6A") (pintype "passive"))
      (node (ref "SV5") (pin "6B") (pinfunction "12_6B") (pintype "passive"))
    )
    (net (code "110") (name "Net-(SV5-13)") (class "Default")
      (node (ref "CRM") (pin "E") (pinfunction "E_E") (pintype "passive"))
      (node (ref "SV5") (pin "7A") (pinfunction "13_7A") (pintype "passive"))
    )
    (net (code "111") (name "Net-(SV5-14)") (class "Default")
      (node (ref "CRM") (pin "S") (pinfunction "S_S") (pintype "passive"))
      (node (ref "SV5") (pin "7B") (pinfunction "14_7B") (pintype "passive"))
    )
    (net (code "112") (name "Net-(SV5-15)") (class "Default")
      (node (ref "R46") (pin "2") (pinfunction "2_2") (pintype "passive"))
      (node (ref "SV5") (pin "8A") (pinfunction "15_8A") (pintype "passive"))
      (node (ref "SV5") (pin "8B") (pinfunction "16_8B") (pintype "passive"))
    )
    (net (code "113") (name "Net-(SV5-17)") (class "Default")
      (node (ref "GAIN") (pin "S") (pinfunction "S_S") (pintype "passive"))
      (node (ref "SV5") (pin "9A") (pinfunction "17_9A") (pintype "passive"))
      (node (ref "SV5") (pin "9B") (pinfunction "18_9B") (pintype "passive"))
    )
    (net (code "114") (name "Net-(SV5-19)") (class "Default")
      (node (ref "GAIN") (pin "A") (pinfunction "A_A") (pintype "passive"))
      (node (ref "SV5") (pin "10A") (pinfunction "19_10A") (pintype "passive"))
      (node (ref "SV5") (pin "10B") (pinfunction "20_10B") (pintype "passive"))
    )
    (net (code "115") (name "Net-(T2-E)") (class "Default")
      (node (ref "R50") (pin "1") (pinfunction "1_1") (pintype "passive"))
      (node (ref "T2") (pin "3") (pinfunction "E_3") (pintype "passive"))
    )
    (net (code "116") (name "OUT+") (class "Default")
      (node (ref "DSUB1") (pin "4") (pinfunction "M_4") (pintype "passive"))
      (node (ref "R34") (pin "2") (pinfunction "2_2") (pintype "passive"))
      (node (ref "RJ2") (pin "6") (pinfunction "6_6") (pintype "passive"))
    )
    (net (code "117") (name "OUT-") (class "Default")
      (node (ref "DSUB1") (pin "5") (pinfunction "M_5") (pintype "passive"))
      (node (ref "R35") (pin "2") (pinfunction "2_2") (pintype "passive"))
      (node (ref "RJ2") (pin "3") (pinfunction "3_3") (pintype "passive"))
    )
    (net (code "118") (name "POTI_JEL") (class "Default")
      (node (ref "C13") (pin "2") (pinfunction "2_2") (pintype "passive"))
      (node (ref "POTI") (pin "7") (pinfunction "7_7") (pintype "passive"))
      (node (ref "POTI") (pin "8") (pinfunction "8_8") (pintype "passive"))
    )
    (net (code "119") (name "SP") (class "Default")
      (node (ref "JUMPER") (pin "5") (pinfunction "5_5") (pintype "passive"))
      (node (ref "POTI") (pin "10") (pinfunction "10_10") (pintype "passive"))
      (node (ref "POTI") (pin "9") (pinfunction "9_9") (pintype "passive"))
    )
    (net (code "120") (name "SPM") (class "Default")
      (node (ref "DIGIT") (pin "5") (pinfunction "5_5") (pintype "passive"))
      (node (ref "DIGIT") (pin "6") (pinfunction "6_6") (pintype "passive"))
      (node (ref "IC3") (pin "10") (pinfunction "B_10") (pintype "input"))
    )
    (net (code "121") (name "SPOUT") (class "Default")
      (node (ref "C60") (pin "2") (pinfunction "2_2") (pintype "passive"))
      (node (ref "C71") (pin "2") (pinfunction "2_2") (pintype "passive"))
      (node (ref "IC11") (pin "15") (pinfunction "ROUT_15") (pintype "output"))
      (node (ref "L10") (pin "1") (pinfunction "1_1") (pintype "passive"))
    )
    (net (code "122") (name "VDD") (class "Default")
      (node (ref "C26") (pin "1") (pinfunction "1_1") (pintype "passive"))
      (node (ref "C57") (pin "+") (pinfunction "+_+") (pintype "passive"))
      (node (ref "C58") (pin "1") (pinfunction "1_1") (pintype "passive"))
      (node (ref "IC1") (pin "8") (pinfunction "V+_8") (pintype "power_in"))
      (node (ref "IC11") (pin "19") (pinfunction "AVCC_19") (pintype "input"))
      (node (ref "IC11") (pin "2") (pinfunction "~{SD}_2") (pintype "input"))
      (node (ref "IC11") (pin "20") (pinfunction "AVCC_20") (pintype "input"))
      (node (ref "IC2") (pin "8") (pinfunction "V+_8") (pintype "power_in"))
      (node (ref "IC4") (pin "8") (pinfunction "V+_8") (pintype "power_in"))
      (node (ref "R1") (pin "2") (pinfunction "2_2") (pintype "passive"))
      (node (ref "R51") (pin "1") (pinfunction "1_1") (pintype "passive"))
      (node (ref "SJ2") (pin "1") (pinfunction "1_1") (pintype "passive"))
    )
    (net (code "123") (name "VSS") (class "Default")
      (node (ref "C27") (pin "2") (pinfunction "2_2") (pintype "passive"))
      (node (ref "IC1") (pin "4") (pinfunction "V-_4") (pintype "power_in"))
      (node (ref "IC2") (pin "4") (pinfunction "V-_4") (pintype "power_in"))
      (node (ref "IC3") (pin "7") (pinfunction "VEE_7") (pintype "power_in"))
      (node (ref "IC4") (pin "4") (pinfunction "V-_4") (pintype "power_in"))
      (node (ref "SJ1") (pin "1") (pinfunction "1_1") (pintype "passive"))
    )
    (net (code "124") (name "X0") (class "Default")
      (node (ref "IC3") (pin "12") (pinfunction "X0_12") (pintype "bidirectional"))
      (node (ref "JUMPER") (pin "3") (pinfunction "3_3") (pintype "passive"))
    )
    (net (code "125") (name "unconnected-(IC12-GND-Pad2)") (class "Default")
      (node (ref "IC12") (pin "2") (pinfunction "GND_2") (pintype "passive"))
    )
    (net (code "126") (name "unconnected-(IC12-VI-Pad1)") (class "Default")
      (node (ref "IC12") (pin "1") (pinfunction "VI_1") (pintype "input"))
    )
    (net (code "127") (name "unconnected-(IC12-VO-Pad3)") (class "Default")
      (node (ref "IC12") (pin "3") (pinfunction "VO_3") (pintype "passive"))
    )
    (net (code "128") (name "unconnected-(JUMPER-Pad2)") (class "Default")
      (node (ref "JUMPER") (pin "2") (pinfunction "2_2") (pintype "passive"))
    )
    (net (code "129") (name "unconnected-(POTI-Pad4)") (class "Default")
      (node (ref "POTI") (pin "4") (pinfunction "4_4") (pintype "passive"))
    )
    (net (code "130") (name "unconnected-(PROG-Pad2)") (class "Default")
      (node (ref "PROG") (pin "2") (pinfunction "2_2") (pintype "passive"))
    )
    (net (code "131") (name "unconnected-(PROG-Pad10)") (class "Default")
      (node (ref "PROG") (pin "10") (pinfunction "10_10") (pintype "passive"))
    )
    (net (code "132") (name "unconnected-(SD2-PadSZAB)") (class "Default")
      (node (ref "SD2") (pin "SZAB") (pinfunction "SZAB_SZAB") (pintype "bidirectional"))
    )
    (net (code "133") (name "unconnected-(SV5-3-Pad2A)") (class "Default")
      (node (ref "SV5") (pin "2A") (pinfunction "3_2A") (pintype "passive"))
    )
    (net (code "134") (name "unconnected-(SV7-Pad1)") (class "Default")
      (node (ref "SV7") (pin "1") (pinfunction "1_1") (pintype "passive"))
    )
    (net (code "135") (name "unconnected-(SV7-Pad2)") (class "Default")
      (node (ref "SV7") (pin "2") (pinfunction "2_2") (pintype "passive"))
    )
    (net (code "136") (name "unconnected-(SV7-Pad3)") (class "Default")
      (node (ref "SV7") (pin "3") (pinfunction "3_3") (pintype "passive"))
    )
    (net (code "137") (name "unconnected-(SV7-Pad4)") (class "Default")
      (node (ref "SV7") (pin "4") (pinfunction "4_4") (pintype "passive"))
    )
    (net (code "138") (name "unconnected-(SV7-Pad5)") (class "Default")
      (node (ref "SV7") (pin "5") (pinfunction "5_5") (pintype "passive"))
    )
    (net (code "139") (name "unconnected-(SV7-Pad6)") (class "Default")
      (node (ref "SV7") (pin "6") (pinfunction "6_6") (pintype "passive"))
    )
    (net (code "140") (name "unconnected-(SV8-Pad1)") (class "Default")
      (node (ref "SV8") (pin "1") (pinfunction "1_1") (pintype "passive"))
    )
    (net (code "141") (name "unconnected-(SV8-Pad2)") (class "Default")
      (node (ref "SV8") (pin "2") (pinfunction "2_2") (pintype "passive"))
    )
    (net (code "142") (name "unconnected-(SV8-Pad3)") (class "Default")
      (node (ref "SV8") (pin "3") (pinfunction "3_3") (pintype "passive"))
    )
    (net (code "143") (name "unconnected-(SV8-Pad4)") (class "Default")
      (node (ref "SV8") (pin "4") (pinfunction "4_4") (pintype "passive"))
    )
    (net (code "144") (name "unconnected-(SV8-Pad5)") (class "Default")
      (node (ref "SV8") (pin "5") (pinfunction "5_5") (pintype "passive"))
    )
    (net (code "145") (name "unconnected-(SV8-Pad6)") (class "Default")
      (node (ref "SV8") (pin "6") (pinfunction "6_6") (pintype "passive"))
    )
    (net (code "146") (name "unconnected-(SV9-Pad1)") (class "Default")
      (node (ref "SV9") (pin "1") (pinfunction "1_1") (pintype "passive"))
    )
    (net (code "147") (name "unconnected-(SV9-Pad2)") (class "Default")
      (node (ref "SV9") (pin "2") (pinfunction "2_2") (pintype "passive"))
    )
    (net (code "148") (name "unconnected-(SV9-Pad3)") (class "Default")
      (node (ref "SV9") (pin "3") (pinfunction "3_3") (pintype "passive"))
    )
    (net (code "149") (name "unconnected-(SV9-Pad4)") (class "Default")
      (node (ref "SV9") (pin "4") (pinfunction "4_4") (pintype "passive"))
    )
    (net (code "150") (name "unconnected-(SV9-Pad5)") (class "Default")
      (node (ref "SV9") (pin "5") (pinfunction "5_5") (pintype "passive"))
    )
    (net (code "151") (name "unconnected-(SV9-Pad6)") (class "Default")
      (node (ref "SV9") (pin "6") (pinfunction "6_6") (pintype "passive"))
    )
    (net (code "152") (name "~{MCLR}") (class "Default")
      (node (ref "PROG") (pin "5") (pinfunction "5_5") (pintype "passive"))
      (node (ref "TAP") (pin "1") (pinfunction "1_1") (pintype "passive"))
      (node (ref "TAP") (pin "2") (pinfunction "2_2") (pintype "passive"))
    )
  )
)
